# Schematic.net
KiCad netlist of a schematic drawn in Altium Designer
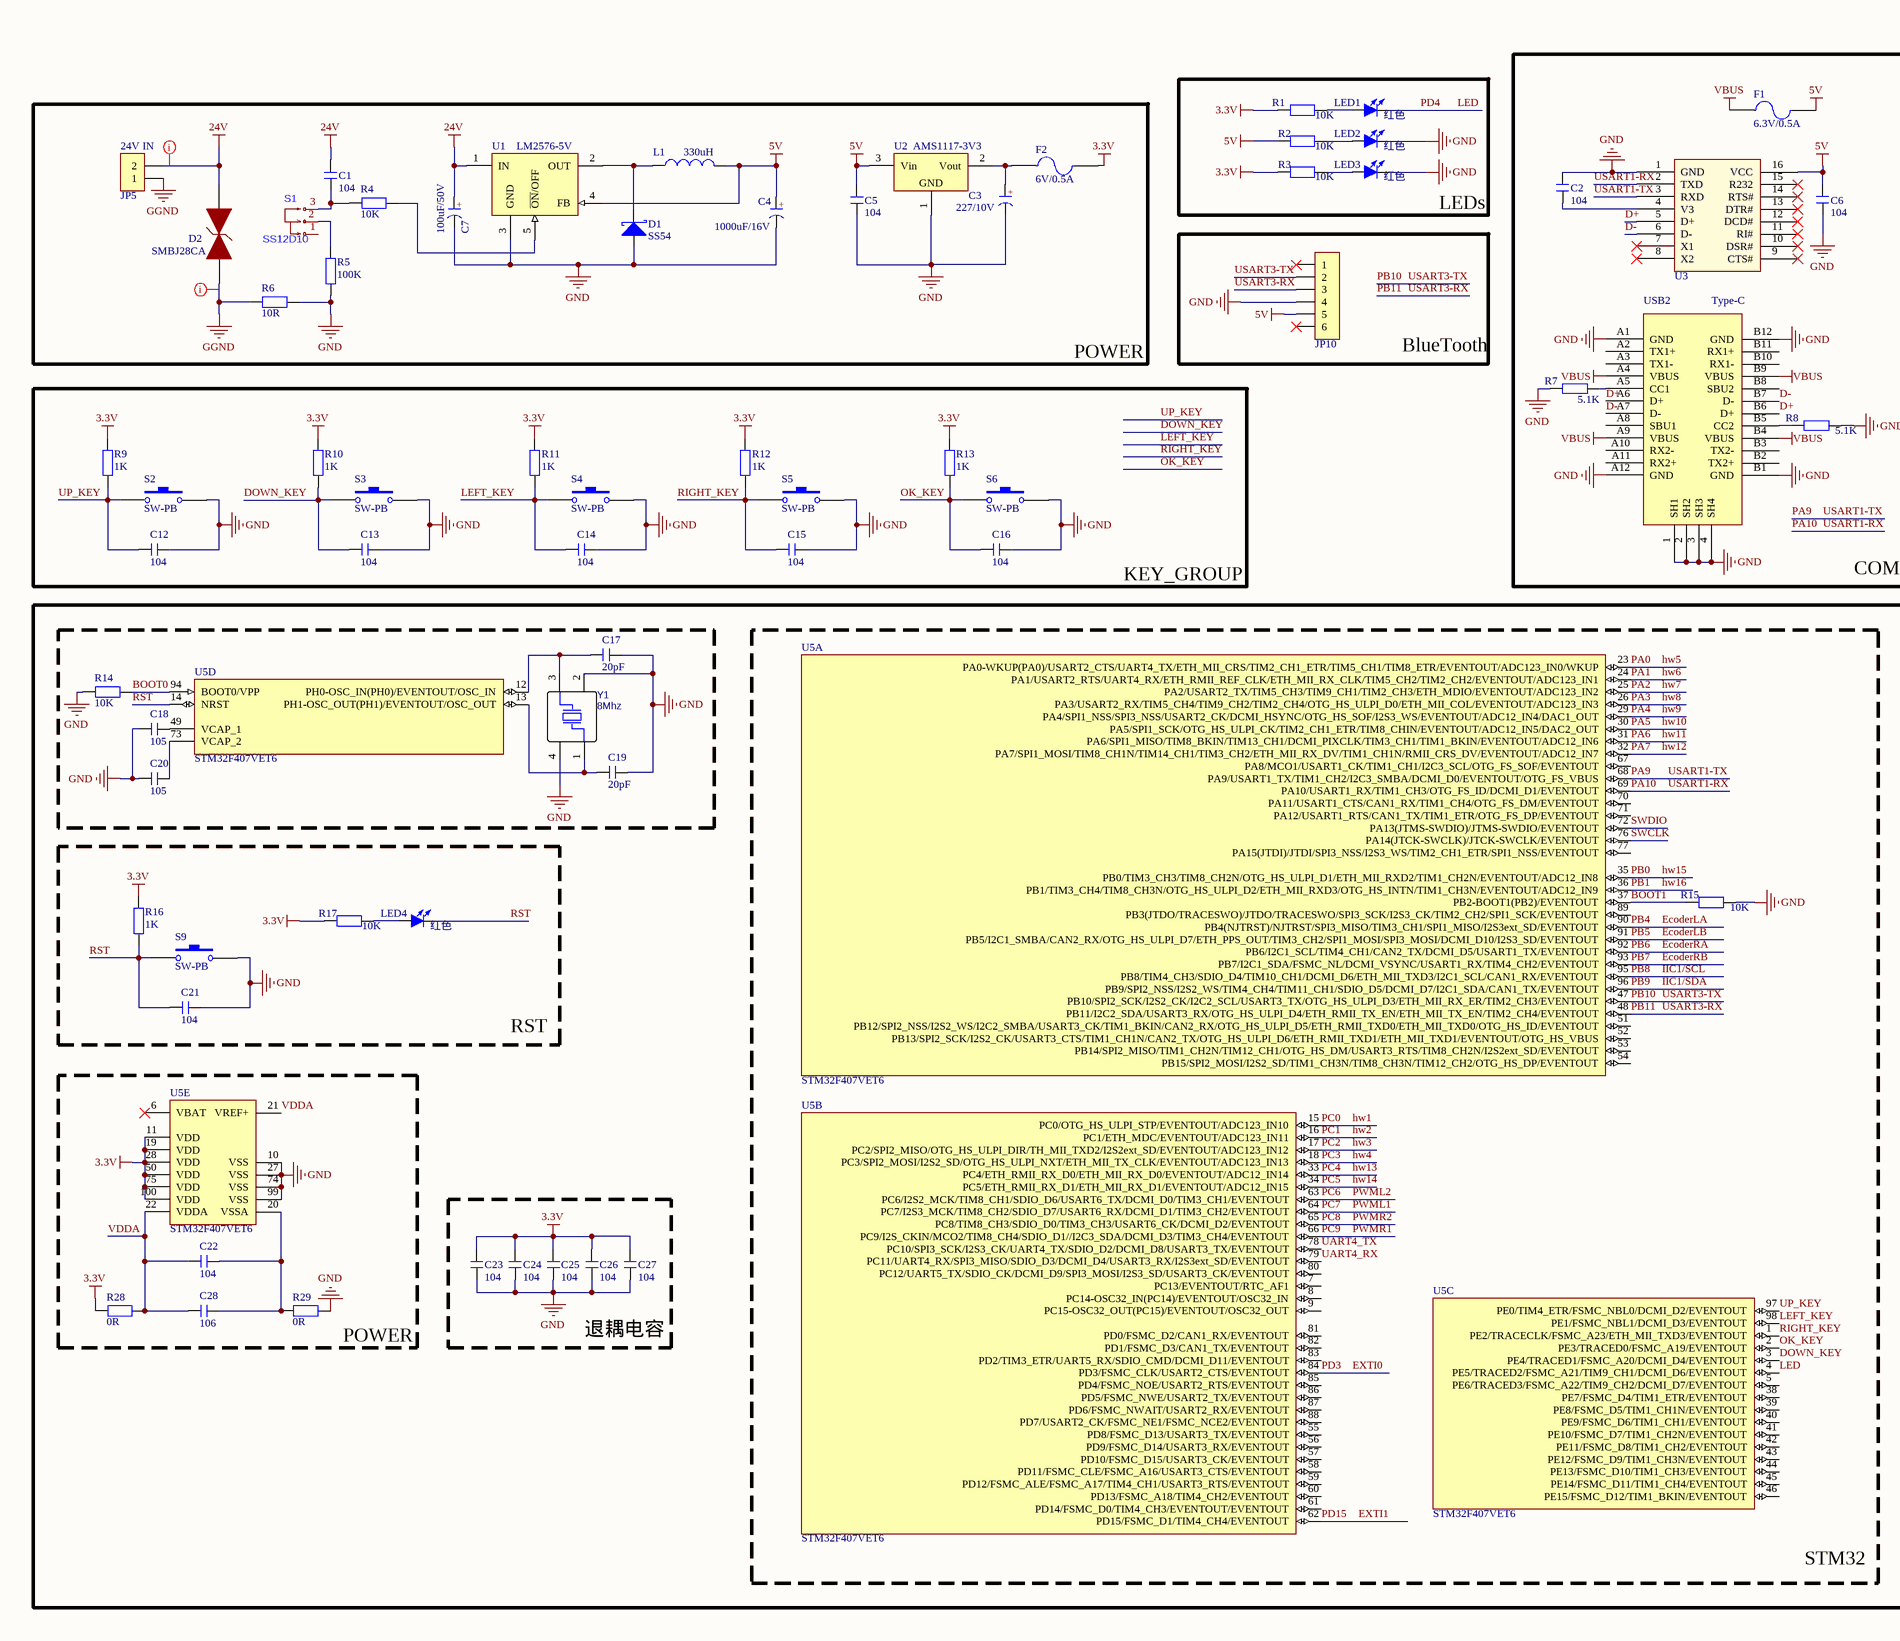
[diagram p0: Schematic.SchDoc, left]
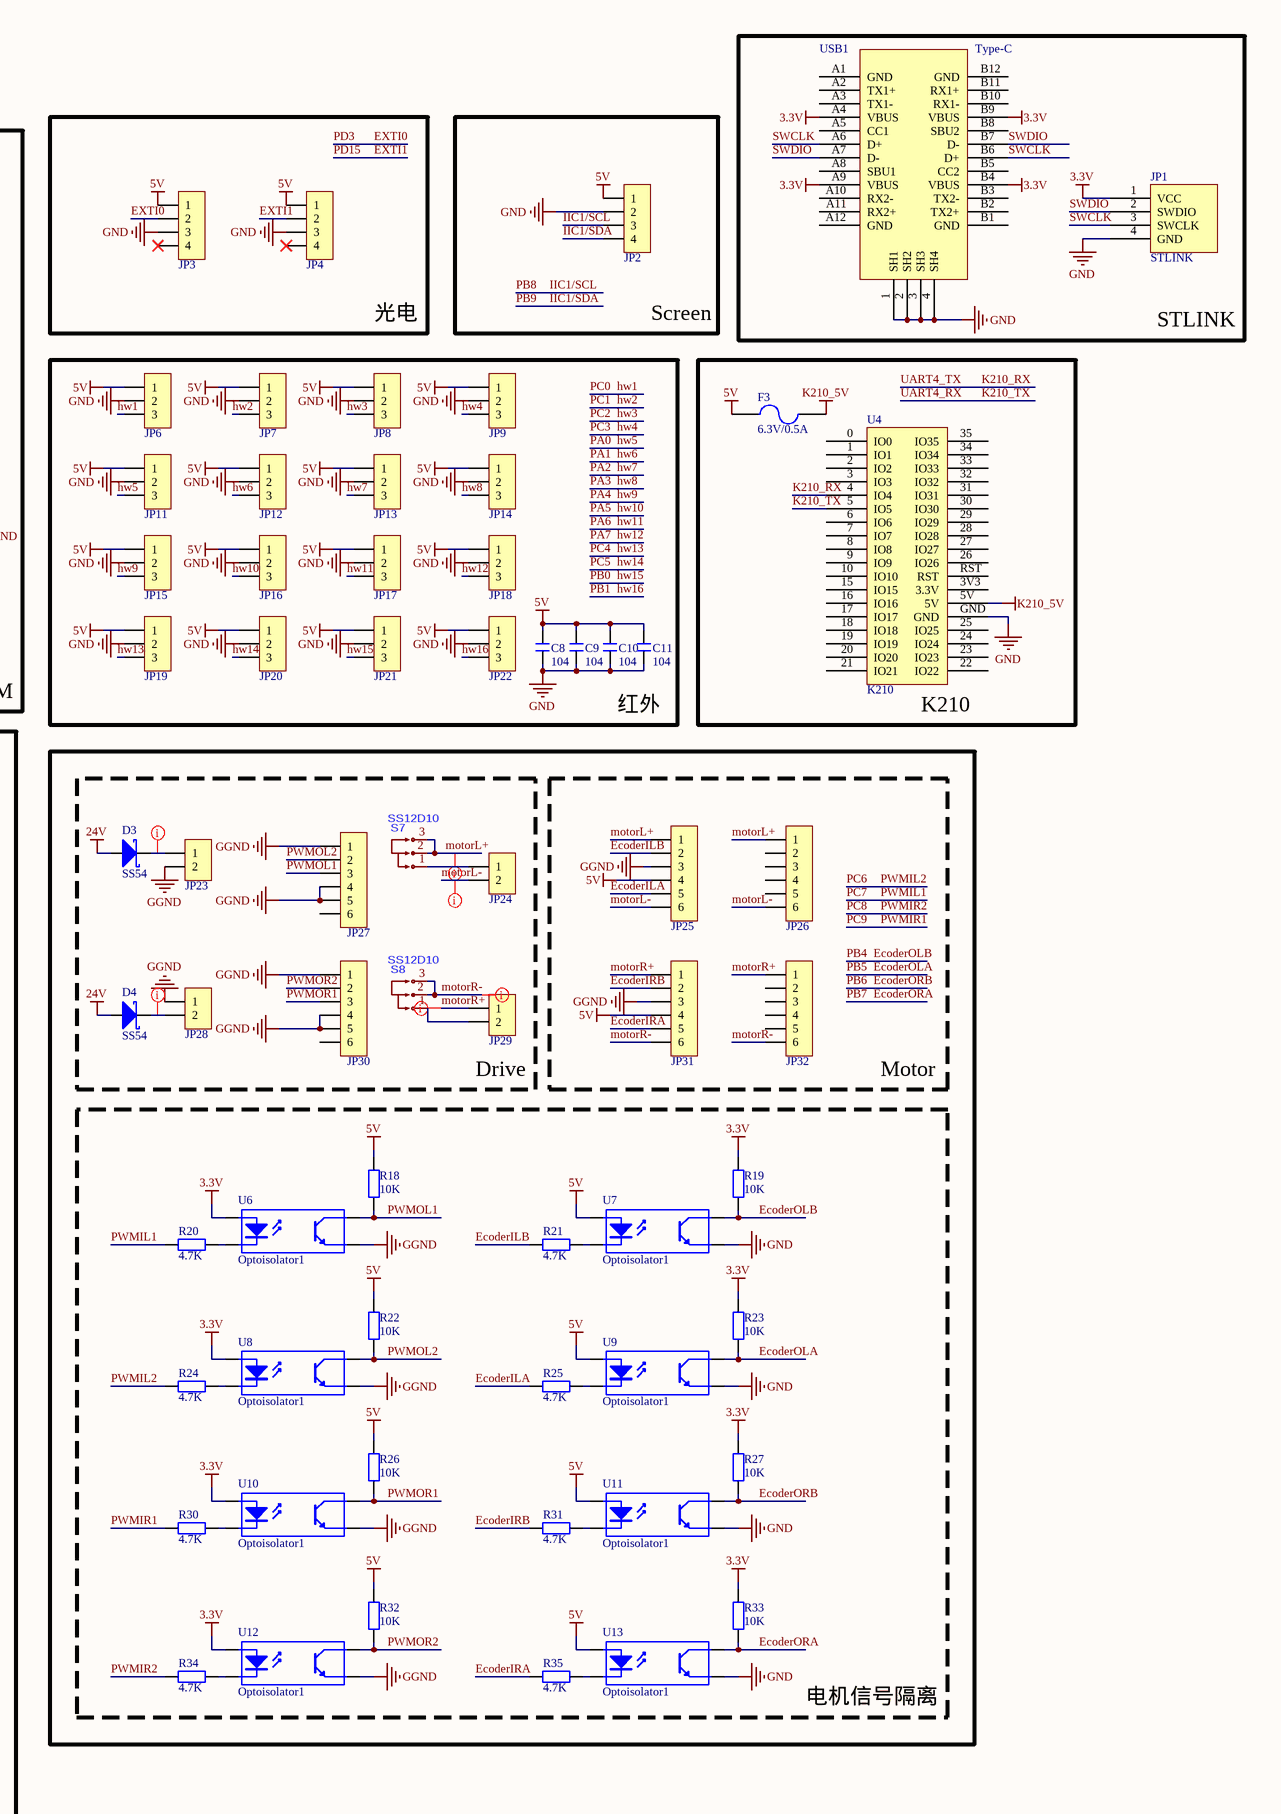
[diagram p1: Schematic.SchDoc, right]

(export (version "E")
  (design (tool "Eeschema 10.0.6"))
  (components
    (comp (ref "C1")
      (value "104")
      (footprint "C 0805_L")
      (description "贴片电容")
      (libsource (lib "0.1 - 电阻-电容-电感") (part "C"))
    )
    (comp (ref "C2") (value "104") (footprint "C 0805_L") (libsource (lib "0.1 - 电阻-电容-电感") (part "C")))
    (comp (ref "C3")
      (value "227/10V")
      (footprint "CM D(6.3*7.7)")
      (description "贴片钽电容")
      (libsource (lib "0.1 - 电阻-电容-电感") (part "CT"))
    )
    (comp (ref "C4")
      (value "1000uF/16V")
      (footprint "CAP 7.5*16*25 - GD")
      (description "直插电解电容")
      (libsource (lib "0.1 - 电阻-电容-电感") (part "CE"))
    )
    (comp (ref "C5")
      (value "104")
      (footprint "C 0805_L")
      (description "无极性贴片电容")
      (fields (field (name "版权归属") "源创客"))
      (libsource (lib "电阻-电容-电感") (part "C"))
    )
    (comp (ref "C6") (value "104") (footprint "C 0805_L") (libsource (lib "0.1 - 电阻-电容-电感") (part "C")))
    (comp (ref "C7")
      (value "100uF/50V")
      (footprint "CAP 3.5*8*11.5 - GD")
      (description "直插固态电容")
      (fields (field (name "版权归属") "封装库来自淘宝 ID：黄晶宝石"))
      (libsource (lib "0.1 - 电阻-电容-电感") (part "CS"))
    )
    (comp (ref "C8") (value "104") (footprint "C 0805_L") (libsource (lib "0.1 - 电阻-电容-电感") (part "C")))
    (comp (ref "C9") (value "104") (footprint "C 0805_L") (libsource (lib "0.1 - 电阻-电容-电感") (part "C")))
    (comp (ref "C10") (value "104") (footprint "C 0805_L") (libsource (lib "0.1 - 电阻-电容-电感") (part "C")))
    (comp (ref "C11") (value "104") (footprint "C 0805_L") (libsource (lib "0.1 - 电阻-电容-电感") (part "C")))
    (comp (ref "C12")
      (value "104")
      (footprint "C 0805_L")
      (description "贴片电容")
      (libsource (lib "0.1 - 电阻-电容-电感") (part "C"))
    )
    (comp (ref "C13")
      (value "104")
      (footprint "C 0805_L")
      (description "贴片电容")
      (libsource (lib "0.1 - 电阻-电容-电感") (part "C"))
    )
    (comp (ref "C14")
      (value "104")
      (footprint "C 0805_L")
      (description "贴片电容")
      (libsource (lib "0.1 - 电阻-电容-电感") (part "C"))
    )
    (comp (ref "C15")
      (value "104")
      (footprint "C 0805_L")
      (description "贴片电容")
      (libsource (lib "0.1 - 电阻-电容-电感") (part "C"))
    )
    (comp (ref "C16")
      (value "104")
      (footprint "C 0805_L")
      (description "贴片电容")
      (libsource (lib "0.1 - 电阻-电容-电感") (part "C"))
    )
    (comp (ref "C17")
      (value "20pF")
      (footprint "C 0805_L")
      (description "贴片电容")
      (libsource (lib "0.1 - 电阻-电容-电感") (part "C"))
    )
    (comp (ref "C18")
      (value "105")
      (footprint "C 0805_L")
      (description "贴片电容")
      (libsource (lib "0.1 - 电阻-电容-电感") (part "C"))
    )
    (comp (ref "C19")
      (value "20pF")
      (footprint "C 0805_L")
      (description "贴片电容")
      (libsource (lib "0.1 - 电阻-电容-电感") (part "C"))
    )
    (comp (ref "C20")
      (value "105")
      (footprint "C 0805_L")
      (description "贴片电容")
      (libsource (lib "0.1 - 电阻-电容-电感") (part "C"))
    )
    (comp (ref "C21")
      (value "104")
      (footprint "C 0805_L")
      (description "贴片电容")
      (libsource (lib "0.1 - 电阻-电容-电感") (part "C"))
    )
    (comp (ref "C22")
      (value "104")
      (footprint "C 0805_L")
      (description "贴片电容")
      (libsource (lib "0.1 - 电阻-电容-电感") (part "C"))
    )
    (comp (ref "C23")
      (value "104")
      (footprint "C 0805_L")
      (description "无极性贴片电容")
      (fields (field (name "版权归属") "源创客"))
      (libsource (lib "电阻-电容-电感") (part "C"))
    )
    (comp (ref "C24")
      (value "104")
      (footprint "C 0805_L")
      (description "无极性贴片电容")
      (fields (field (name "版权归属") "源创客"))
      (libsource (lib "电阻-电容-电感") (part "C"))
    )
    (comp (ref "C25")
      (value "104")
      (footprint "C 0805_L")
      (description "无极性贴片电容")
      (fields (field (name "版权归属") "源创客"))
      (libsource (lib "电阻-电容-电感") (part "C"))
    )
    (comp (ref "C26")
      (value "104")
      (footprint "C 0805_L")
      (description "无极性贴片电容")
      (fields (field (name "版权归属") "源创客"))
      (libsource (lib "电阻-电容-电感") (part "C"))
    )
    (comp (ref "C27")
      (value "104")
      (footprint "C 0805_L")
      (description "无极性贴片电容")
      (fields (field (name "版权归属") "源创客"))
      (libsource (lib "电阻-电容-电感") (part "C"))
    )
    (comp (ref "C28")
      (value "106")
      (footprint "C 0805_L")
      (description "贴片电容")
      (libsource (lib "0.1 - 电阻-电容-电感") (part "C"))
    )
    (comp (ref "D1")
      (value "SS54")
      (footprint "SMB/DO214AA")
      (description "肖特基二极管  30V/5A")
      (libsource (lib "0.2 -  二极管-整流桥") (part "1N5824"))
    )
    (comp (ref "D2")
      (value "SMBJ28CA")
      (footprint "SMB/DO214AA")
      (libsource (lib "MyPcbLib") (part "SMBJ28CA"))
    )
    (comp (ref "D3")
      (value "SS54")
      (footprint "SMB/DO214AA")
      (description "肖特基二极管  30V/5A")
      (libsource (lib "0.2 -  二极管-整流桥") (part "1N5824"))
    )
    (comp (ref "D4")
      (value "SS54")
      (footprint "SMB/DO214AA")
      (description "肖特基二极管  30V/5A")
      (libsource (lib "0.2 -  二极管-整流桥") (part "1N5824"))
    )
    (comp (ref "F1")
      (value "6.3V/0.5A")
      (footprint "C 0805_L")
      (description "Fuse")
      (fields (field (name "PUBLISHER") "Altium Limited"))
      (libsource (lib "Miscellaneous Devices") (part "Fuse 2"))
    )
    (comp (ref "F2")
      (value "6V/0.5A")
      (footprint "R 1206_L")
      (description "Fuse")
      (fields (field (name "PUBLISHER") "Altium Limited"))
      (libsource (lib "Miscellaneous Devices") (part "Fuse 2"))
    )
    (comp (ref "F3")
      (value "6.3V/0.5A")
      (footprint "C 0805_L")
      (description "Fuse")
      (fields (field (name "PUBLISHER") "Altium Limited"))
      (libsource (lib "Miscellaneous Devices") (part "Fuse 2"))
    )
    (comp (ref "JP1") (value "STLINK") (footprint "HDR2.54-LI-4P") (libsource (lib "SCHLib") (part "STLINK")))
    (comp (ref "JP2")
      (value "OLED")
      (footprint "OLED_0.96 4P")
      (libsource (lib "18 - 接插件-脚距2.54mm (100mil) ") (part "Header 4"))
    )
    (comp (ref "JP3")
      (value "光电")
      (footprint "XH2.54-LI-4P")
      (description "4P接插件")
      (libsource (lib "18 - 接插件-脚距2.54mm (100mil) ") (part "Header 4"))
    )
    (comp (ref "JP4")
      (value "光电")
      (footprint "XH2.54-LI-4P")
      (description "4P接插件")
      (libsource (lib "18 - 接插件-脚距2.54mm (100mil) ") (part "Header 4"))
    )
    (comp (ref "JP5")
      (value "24V IN")
      (footprint "KF128-5.08-2P")
      (description "2P接插件")
      (fields (field (name "版权归属") "封装库来自淘宝卖家 ID：黄晶宝石"))
      (libsource (lib "") (part "Header 2_1"))
    )
    (comp (ref "JP6")
      (value "红外")
      (footprint "PH2.0-LI-3P")
      (description "3P接插件")
      (fields (field (name "版权归属") "源创客"))
      (libsource (lib "p-接插件") (part "Header 3"))
    )
    (comp (ref "JP7")
      (value "红外")
      (footprint "PH2.0-LI-3P")
      (description "3P接插件")
      (fields (field (name "版权归属") "源创客"))
      (libsource (lib "p-接插件") (part "Header 3"))
    )
    (comp (ref "JP8")
      (value "红外")
      (footprint "PH2.0-LI-3P")
      (description "3P接插件")
      (fields (field (name "版权归属") "源创客"))
      (libsource (lib "p-接插件") (part "Header 3"))
    )
    (comp (ref "JP9")
      (value "红外")
      (footprint "PH2.0-LI-3P")
      (description "3P接插件")
      (fields (field (name "版权归属") "源创客"))
      (libsource (lib "p-接插件") (part "Header 3"))
    )
    (comp (ref "JP10")
      (value "蓝牙")
      (footprint "HDR2.54-LI-6P")
      (description "6P接插件")
      (libsource (lib "18 - 接插件-脚距2.54mm (100mil) ") (part "Header 6"))
    )
    (comp (ref "JP11")
      (value "红外")
      (footprint "PH2.0-LI-3P")
      (description "3P接插件")
      (fields (field (name "版权归属") "源创客"))
      (libsource (lib "p-接插件") (part "Header 3"))
    )
    (comp (ref "JP12")
      (value "红外")
      (footprint "PH2.0-LI-3P")
      (description "3P接插件")
      (fields (field (name "版权归属") "源创客"))
      (libsource (lib "p-接插件") (part "Header 3"))
    )
    (comp (ref "JP13")
      (value "红外")
      (footprint "PH2.0-LI-3P")
      (description "3P接插件")
      (fields (field (name "版权归属") "源创客"))
      (libsource (lib "p-接插件") (part "Header 3"))
    )
    (comp (ref "JP14")
      (value "红外")
      (footprint "PH2.0-LI-3P")
      (description "3P接插件")
      (fields (field (name "版权归属") "源创客"))
      (libsource (lib "p-接插件") (part "Header 3"))
    )
    (comp (ref "JP15")
      (value "红外")
      (footprint "PH2.0-LI-3P")
      (description "3P接插件")
      (fields (field (name "版权归属") "源创客"))
      (libsource (lib "p-接插件") (part "Header 3"))
    )
    (comp (ref "JP16")
      (value "红外")
      (footprint "PH2.0-LI-3P")
      (description "3P接插件")
      (fields (field (name "版权归属") "源创客"))
      (libsource (lib "p-接插件") (part "Header 3"))
    )
    (comp (ref "JP17")
      (value "红外")
      (footprint "PH2.0-LI-3P")
      (description "3P接插件")
      (fields (field (name "版权归属") "源创客"))
      (libsource (lib "p-接插件") (part "Header 3"))
    )
    (comp (ref "JP18")
      (value "红外")
      (footprint "PH2.0-LI-3P")
      (description "3P接插件")
      (fields (field (name "版权归属") "源创客"))
      (libsource (lib "p-接插件") (part "Header 3"))
    )
    (comp (ref "JP19")
      (value "红外")
      (footprint "PH2.0-LI-3P")
      (description "3P接插件")
      (fields (field (name "版权归属") "源创客"))
      (libsource (lib "p-接插件") (part "Header 3"))
    )
    (comp (ref "JP20")
      (value "红外")
      (footprint "PH2.0-LI-3P")
      (description "3P接插件")
      (fields (field (name "版权归属") "源创客"))
      (libsource (lib "p-接插件") (part "Header 3"))
    )
    (comp (ref "JP21")
      (value "红外")
      (footprint "PH2.0-LI-3P")
      (description "3P接插件")
      (fields (field (name "版权归属") "源创客"))
      (libsource (lib "p-接插件") (part "Header 3"))
    )
    (comp (ref "JP22")
      (value "红外")
      (footprint "PH2.0-LI-3P")
      (description "3P接插件")
      (fields (field (name "版权归属") "源创客"))
      (libsource (lib "p-接插件") (part "Header 3"))
    )
    (comp (ref "JP23")
      (value "驱动1")
      (footprint "KF128-5.08-2P")
      (description "2P接插件")
      (fields (field (name "版权归属") "封装库来自淘宝卖家 ID：黄晶宝石"))
      (libsource (lib "6.1 - 接插件-脚距5.08 (200mil) ") (part "Header 2"))
    )
    (comp (ref "JP24")
      (value "驱动输出1")
      (footprint "KF128-5.08-2P")
      (description "2P接插件")
      (fields (field (name "版权归属") "封装库来自淘宝卖家 ID：黄晶宝石"))
      (libsource (lib "6.1 - 接插件-脚距5.08 (200mil) ") (part "Header 2"))
    )
    (comp (ref "JP25")
      (value "电机1")
      (footprint "XH2.54-LI-6P")
      (description "6P接插件")
      (fields (field (name "版权归属") "封装库来自淘宝 ID：黄晶宝石"))
      (libsource (lib "5.4 - 接插件-脚距2.54 (100mil) ") (part "Header 6"))
    )
    (comp (ref "JP26")
      (value "电机1p")
      (footprint "XH2.54-LI-6P")
      (description "6P接插件")
      (libsource (lib "18 - 接插件-脚距2.54mm (100mil) ") (part "Header 6"))
    )
    (comp (ref "JP27")
      (value "驱动pwm1")
      (footprint "XH2.54-LI-6P")
      (description "6P接插件")
      (fields (field (name "版权归属") "封装库来自淘宝 ID：黄晶宝石"))
      (libsource (lib "5.4 - 接插件-脚距2.54 (100mil) ") (part "Header 6"))
    )
    (comp (ref "JP28")
      (value "驱动2")
      (footprint "KF128-5.08-2P")
      (description "2P接插件")
      (fields (field (name "版权归属") "封装库来自淘宝卖家 ID：黄晶宝石"))
      (libsource (lib "6.1 - 接插件-脚距5.08 (200mil) ") (part "Header 2"))
    )
    (comp (ref "JP29")
      (value "驱动输出1")
      (footprint "KF128-5.08-2P")
      (description "2P接插件")
      (fields (field (name "版权归属") "封装库来自淘宝卖家 ID：黄晶宝石"))
      (libsource (lib "6.1 - 接插件-脚距5.08 (200mil) ") (part "Header 2"))
    )
    (comp (ref "JP30")
      (value "驱动pwm2")
      (footprint "XH2.54-LI-6P")
      (description "6P接插件")
      (fields (field (name "版权归属") "封装库来自淘宝 ID：黄晶宝石"))
      (libsource (lib "5.4 - 接插件-脚距2.54 (100mil) ") (part "Header 6"))
    )
    (comp (ref "JP31")
      (value "电机2")
      (footprint "XH2.54-LI-6P")
      (description "6P接插件")
      (fields (field (name "版权归属") "封装库来自淘宝 ID：黄晶宝石"))
      (libsource (lib "5.4 - 接插件-脚距2.54 (100mil) ") (part "Header 6"))
    )
    (comp (ref "JP32")
      (value "电机2p")
      (footprint "XH2.54-LI-6P")
      (description "6P接插件")
      (libsource (lib "18 - 接插件-脚距2.54mm (100mil) ") (part "Header 6"))
    )
    (comp (ref "L1")
      (value "330uH")
      (footprint "CDRH125")
      (description "Inductor")
      (fields (field (name "PUBLISHER") "Altium Limited"))
      (libsource (lib "安中医库2.0") (part "电感直插"))
    )
    (comp (ref "LED1")
      (value "红色")
      (footprint "LED 0805G")
      (description "贴片LED")
      (fields (field (name "版权归属") "封装库来自淘宝 ID：黄晶宝石"))
      (libsource (lib "0.3 - LED发光二极管") (part "LED-SMD"))
    )
    (comp (ref "LED2")
      (value "红色")
      (footprint "LED 0805G")
      (description "贴片LED")
      (fields (field (name "版权归属") "封装库来自淘宝 ID：黄晶宝石"))
      (libsource (lib "0.3 - LED发光二极管") (part "LED-SMD"))
    )
    (comp (ref "LED3")
      (value "红色")
      (footprint "LED 0805G")
      (description "贴片LED")
      (fields (field (name "版权归属") "封装库来自淘宝 ID：黄晶宝石"))
      (libsource (lib "0.3 - LED发光二极管") (part "LED-SMD"))
    )
    (comp (ref "LED4")
      (value "红色")
      (footprint "LED 0805G")
      (description "贴片LED")
      (fields (field (name "版权归属") "封装库来自淘宝 ID：黄晶宝石"))
      (libsource (lib "0.3 - LED发光二极管") (part "LED-SMD"))
    )
    (comp (ref "R1")
      (value "10K")
      (footprint "R 0805_L")
      (description "贴片电阻")
      (fields (field (name "版权归属") "来自淘宝 ID：黄晶宝石"))
      (libsource (lib "0.1 - 电阻-电容-电感") (part "R"))
    )
    (comp (ref "R2")
      (value "10K")
      (footprint "R 0805_L")
      (description "贴片电阻")
      (fields (field (name "版权归属") "来自淘宝 ID：黄晶宝石"))
      (libsource (lib "0.1 - 电阻-电容-电感") (part "R"))
    )
    (comp (ref "R3")
      (value "10K")
      (footprint "R 0805_L")
      (description "贴片电阻")
      (fields (field (name "版权归属") "来自淘宝 ID：黄晶宝石"))
      (libsource (lib "0.1 - 电阻-电容-电感") (part "R"))
    )
    (comp (ref "R4")
      (value "10K")
      (footprint "R 0805_L")
      (description "贴片电阻")
      (fields (field (name "版权归属") "来自淘宝 ID：黄晶宝石"))
      (libsource (lib "0.1 - 电阻-电容-电感") (part "R"))
    )
    (comp (ref "R5")
      (value "100K")
      (footprint "R 0805_L")
      (description "贴片电阻")
      (fields (field (name "版权归属") "来自淘宝 ID：黄晶宝石"))
      (libsource (lib "0.1 - 电阻-电容-电感") (part "R"))
    )
    (comp (ref "R6")
      (value "10R")
      (footprint "R 0805_L")
      (description "贴片电阻")
      (fields (field (name "版权归属") "来自淘宝 ID：黄晶宝石"))
      (libsource (lib "0.1 - 电阻-电容-电感") (part "R"))
    )
    (comp (ref "R7") (value "5.1K") (footprint "R 0805_L") (libsource (lib "EXPLORER") (part "R")))
    (comp (ref "R8") (value "5.1K") (footprint "R 0805_L") (libsource (lib "EXPLORER") (part "R")))
    (comp (ref "R9")
      (value "1K")
      (footprint "R 0805_L")
      (description "贴片电阻")
      (fields (field (name "版权归属") "来自淘宝 ID：黄晶宝石"))
      (libsource (lib "0.1 - 电阻-电容-电感") (part "R"))
    )
    (comp (ref "R10")
      (value "1K")
      (footprint "R 0805_L")
      (description "贴片电阻")
      (fields (field (name "版权归属") "来自淘宝 ID：黄晶宝石"))
      (libsource (lib "0.1 - 电阻-电容-电感") (part "R"))
    )
    (comp (ref "R11")
      (value "1K")
      (footprint "R 0805_L")
      (description "贴片电阻")
      (fields (field (name "版权归属") "来自淘宝 ID：黄晶宝石"))
      (libsource (lib "0.1 - 电阻-电容-电感") (part "R"))
    )
    (comp (ref "R12")
      (value "1K")
      (footprint "R 0805_L")
      (description "贴片电阻")
      (fields (field (name "版权归属") "来自淘宝 ID：黄晶宝石"))
      (libsource (lib "0.1 - 电阻-电容-电感") (part "R"))
    )
    (comp (ref "R13")
      (value "1K")
      (footprint "R 0805_L")
      (description "贴片电阻")
      (fields (field (name "版权归属") "来自淘宝 ID：黄晶宝石"))
      (libsource (lib "0.1 - 电阻-电容-电感") (part "R"))
    )
    (comp (ref "R14")
      (value "10K")
      (footprint "R 0805_L")
      (description "贴片电阻")
      (fields (field (name "版权归属") "来自淘宝 ID：黄晶宝石"))
      (libsource (lib "0.1 - 电阻-电容-电感") (part "R"))
    )
    (comp (ref "R15")
      (value "10K")
      (footprint "R 0805_L")
      (description "贴片电阻")
      (fields (field (name "版权归属") "来自淘宝 ID：黄晶宝石"))
      (libsource (lib "0.1 - 电阻-电容-电感") (part "R"))
    )
    (comp (ref "R16")
      (value "1K")
      (footprint "R 0805_L")
      (description "贴片电阻")
      (fields (field (name "版权归属") "来自淘宝 ID：黄晶宝石"))
      (libsource (lib "0.1 - 电阻-电容-电感") (part "R"))
    )
    (comp (ref "R17")
      (value "10K")
      (footprint "R 0805_L")
      (description "贴片电阻")
      (fields (field (name "版权归属") "来自淘宝 ID：黄晶宝石"))
      (libsource (lib "0.1 - 电阻-电容-电感") (part "R"))
    )
    (comp (ref "R18")
      (value "10K")
      (footprint "R 0805_L")
      (description "Resistor")
      (fields (field (name "PUBLISHER") "Altium Limited"))
      (libsource (lib "") (part "Res2_1"))
    )
    (comp (ref "R19")
      (value "10K")
      (footprint "R 0805_L")
      (description "Resistor")
      (fields (field (name "PUBLISHER") "Altium Limited"))
      (libsource (lib "") (part "Res2_1"))
    )
    (comp (ref "R20")
      (value "4.7K")
      (footprint "R 0805_L")
      (description "Resistor")
      (fields (field (name "PUBLISHER") "Altium Limited"))
      (libsource (lib "Miscellaneous Devices") (part "Res2"))
    )
    (comp (ref "R21")
      (value "4.7K")
      (footprint "R 0805_L")
      (description "Resistor")
      (fields (field (name "PUBLISHER") "Altium Limited"))
      (libsource (lib "Miscellaneous Devices") (part "Res2"))
    )
    (comp (ref "R22")
      (value "10K")
      (footprint "R 0805_L")
      (description "Resistor")
      (fields (field (name "PUBLISHER") "Altium Limited"))
      (libsource (lib "") (part "Res2_1"))
    )
    (comp (ref "R23")
      (value "10K")
      (footprint "R 0805_L")
      (description "Resistor")
      (fields (field (name "PUBLISHER") "Altium Limited"))
      (libsource (lib "") (part "Res2_1"))
    )
    (comp (ref "R24")
      (value "4.7K")
      (footprint "R 0805_L")
      (description "Resistor")
      (fields (field (name "PUBLISHER") "Altium Limited"))
      (libsource (lib "Miscellaneous Devices") (part "Res2"))
    )
    (comp (ref "R25")
      (value "4.7K")
      (footprint "R 0805_L")
      (description "Resistor")
      (fields (field (name "PUBLISHER") "Altium Limited"))
      (libsource (lib "Miscellaneous Devices") (part "Res2"))
    )
    (comp (ref "R26")
      (value "10K")
      (footprint "R 0805_L")
      (description "Resistor")
      (fields (field (name "PUBLISHER") "Altium Limited"))
      (libsource (lib "") (part "Res2_1"))
    )
    (comp (ref "R27")
      (value "10K")
      (footprint "R 0805_L")
      (description "Resistor")
      (fields (field (name "PUBLISHER") "Altium Limited"))
      (libsource (lib "") (part "Res2_1"))
    )
    (comp (ref "R28")
      (value "0R")
      (footprint "R 0805_L")
      (description "贴片电阻")
      (fields (field (name "版权归属") "来自淘宝 ID：黄晶宝石"))
      (libsource (lib "0.1 - 电阻-电容-电感") (part "R"))
    )
    (comp (ref "R29")
      (value "0R")
      (footprint "R 0805_L")
      (description "贴片电阻")
      (fields (field (name "版权归属") "来自淘宝 ID：黄晶宝石"))
      (libsource (lib "0.1 - 电阻-电容-电感") (part "R"))
    )
    (comp (ref "R30")
      (value "4.7K")
      (footprint "R 0805_L")
      (description "Resistor")
      (fields (field (name "PUBLISHER") "Altium Limited"))
      (libsource (lib "Miscellaneous Devices") (part "Res2"))
    )
    (comp (ref "R31")
      (value "4.7K")
      (footprint "R 0805_L")
      (description "Resistor")
      (fields (field (name "PUBLISHER") "Altium Limited"))
      (libsource (lib "Miscellaneous Devices") (part "Res2"))
    )
    (comp (ref "R32")
      (value "10K")
      (footprint "R 0805_L")
      (description "Resistor")
      (fields (field (name "PUBLISHER") "Altium Limited"))
      (libsource (lib "") (part "Res2_1"))
    )
    (comp (ref "R33")
      (value "10K")
      (footprint "R 0805_L")
      (description "Resistor")
      (fields (field (name "PUBLISHER") "Altium Limited"))
      (libsource (lib "") (part "Res2_1"))
    )
    (comp (ref "R34")
      (value "4.7K")
      (footprint "R 0805_L")
      (description "Resistor")
      (fields (field (name "PUBLISHER") "Altium Limited"))
      (libsource (lib "Miscellaneous Devices") (part "Res2"))
    )
    (comp (ref "R35")
      (value "4.7K")
      (footprint "R 0805_L")
      (description "Resistor")
      (fields (field (name "PUBLISHER") "Altium Limited"))
      (libsource (lib "Miscellaneous Devices") (part "Res2"))
    )
    (comp (ref "S1")
      (value "SS12D10")
      (footprint "SS-12D10")
      (libsource (lib "combat") (part "SS12D10G4 071"))
    )
    (comp (ref "S2")
      (value "SW-PB")
      (footprint "TSW SMD-6*6*4.3")
      (description "微动开关")
      (fields (field (name "PUBLISHER") "Altium Limited"))
      (libsource (lib "0.7 - 常用按键-开关") (part "SW-PB"))
    )
    (comp (ref "S3")
      (value "SW-PB")
      (footprint "TSW SMD-6*6*4.3")
      (description "微动开关")
      (fields (field (name "PUBLISHER") "Altium Limited"))
      (libsource (lib "0.7 - 常用按键-开关") (part "SW-PB"))
    )
    (comp (ref "S4")
      (value "SW-PB")
      (footprint "TSW SMD-6*6*4.3")
      (description "微动开关")
      (fields (field (name "PUBLISHER") "Altium Limited"))
      (libsource (lib "0.7 - 常用按键-开关") (part "SW-PB"))
    )
    (comp (ref "S5")
      (value "SW-PB")
      (footprint "TSW SMD-6*6*4.3")
      (description "微动开关")
      (fields (field (name "PUBLISHER") "Altium Limited"))
      (libsource (lib "0.7 - 常用按键-开关") (part "SW-PB"))
    )
    (comp (ref "S6")
      (value "SW-PB")
      (footprint "TSW SMD-6*6*4.3")
      (description "微动开关")
      (fields (field (name "PUBLISHER") "Altium Limited"))
      (libsource (lib "0.7 - 常用按键-开关") (part "SW-PB"))
    )
    (comp (ref "S7")
      (value "SS12D10")
      (footprint "SS-12D10")
      (libsource (lib "combat") (part "SS12D10G4 071"))
    )
    (comp (ref "S8")
      (value "SS12D10")
      (footprint "SS-12D10")
      (libsource (lib "combat") (part "SS12D10G4 071"))
    )
    (comp (ref "S9")
      (value "SW-PB")
      (footprint "TSW SMD-3*6*2.5")
      (description "微动开关")
      (fields (field (name "PUBLISHER") "Altium Limited"))
      (libsource (lib "0.7 - 常用按键-开关") (part "SW-PB"))
    )
    (comp (ref "U1")
      (value "LM2576-5V")
      (footprint "TO263-5A")
      (description "DC降压芯片")
      (libsource (lib "1.1 - 电源类芯片") (part "LM2596-ADJ"))
    )
    (comp (ref "U2")
      (value "AMS1117-3V3")
      (footprint "SOT223_L")
      (description "三端稳压芯片")
      (libsource (lib "1.1 - 电源类芯片") (part "AMS1117"))
    )
    (comp (ref "U3")
      (value "CH340C")
      (footprint "sop16_L")
      (libsource (lib "1.9 - CH340系列编程器芯片") (part "CH340G"))
    )
    (comp (ref "U4") (value "K210") (footprint "K210") (libsource (lib "SCHLib") (part "K210")))
    (comp (ref "U5")
      (value "STM32F407VET6")
      (footprint "LQFP100 14x14_M")
      (libsource (lib "SCHLib") (part "STM32F407VET6"))
    )
    (comp (ref "U6")
      (value "Optoisolator1")
      (footprint "SOP4-W2.54_M")
      (description "光耦隔离")
      (fields (field (name "PUBLISHER") "Altium Limited"))
      (libsource (lib "Miscellaneous Devices") (part "Optoisolator1"))
    )
    (comp (ref "U7")
      (value "Optoisolator1")
      (footprint "SOP4-W2.54_M")
      (description "光耦隔离")
      (fields (field (name "PUBLISHER") "Altium Limited"))
      (libsource (lib "Miscellaneous Devices") (part "Optoisolator1"))
    )
    (comp (ref "U8")
      (value "Optoisolator1")
      (footprint "SOP4-W2.54_M")
      (description "光耦隔离")
      (fields (field (name "PUBLISHER") "Altium Limited"))
      (libsource (lib "Miscellaneous Devices") (part "Optoisolator1"))
    )
    (comp (ref "U9")
      (value "Optoisolator1")
      (footprint "SOP4-W2.54_M")
      (description "光耦隔离")
      (fields (field (name "PUBLISHER") "Altium Limited"))
      (libsource (lib "Miscellaneous Devices") (part "Optoisolator1"))
    )
    (comp (ref "U10")
      (value "Optoisolator1")
      (footprint "SOP4-W2.54_M")
      (description "光耦隔离")
      (fields (field (name "PUBLISHER") "Altium Limited"))
      (libsource (lib "Miscellaneous Devices") (part "Optoisolator1"))
    )
    (comp (ref "U11")
      (value "Optoisolator1")
      (footprint "SOP4-W2.54_M")
      (description "光耦隔离")
      (fields (field (name "PUBLISHER") "Altium Limited"))
      (libsource (lib "Miscellaneous Devices") (part "Optoisolator1"))
    )
    (comp (ref "U12")
      (value "Optoisolator1")
      (footprint "SOP4-W2.54_M")
      (description "光耦隔离")
      (fields (field (name "PUBLISHER") "Altium Limited"))
      (libsource (lib "Miscellaneous Devices") (part "Optoisolator1"))
    )
    (comp (ref "U13")
      (value "Optoisolator1")
      (footprint "SOP4-W2.54_M")
      (description "光耦隔离")
      (fields (field (name "PUBLISHER") "Altium Limited"))
      (libsource (lib "Miscellaneous Devices") (part "Optoisolator1"))
    )
    (comp (ref "USB1")
      (value "Type-C")
      (footprint "USBTypeC-16P")
      (libsource (lib "MyPcbLib") (part "USB-Type-C-TOP"))
    )
    (comp (ref "USB2")
      (value "Type-C")
      (footprint "USBTypeC-16P")
      (libsource (lib "MyPcbLib") (part "USB-Type-C-TOP"))
    )
    (comp (ref "Y1")
      (value "8Mhz")
      (footprint "OSC 5032-4P")
      (fields
        (field (name "BOM_MANUFACTURER PART") "X322516MLB4SI")
        (field (name "BOM_SUPPLIER PART") "C13738")
      )
      (libsource (lib "EXPLORER") (part "Y"))
    )
  )
  (nets
    (net (code "1") (name "/BOOT0") (class "Default")
      (node (ref "R14") (pin "2") (pinfunction "2_2") (pintype "passive"))
      (node (ref "U5") (pin "94") (pinfunction "BOOT0/VPP_94") (pintype "input"))
    )
    (net (code "2") (name "/BOOT1") (class "Default")
      (node (ref "R15") (pin "2") (pinfunction "2_2") (pintype "passive"))
      (node (ref "U5") (pin "37") (pinfunction "PB2-BOOT1(PB2)/EVENTOUT_37") (pintype "bidirectional"))
    )
    (net (code "3") (name "/D+") (class "Default")
      (node (ref "U3") (pin "5") (pinfunction "D+_5") (pintype "passive"))
      (node (ref "USB2") (pin "A6") (pinfunction "D+_A6") (pintype "passive"))
      (node (ref "USB2") (pin "B6") (pinfunction "D+_B6") (pintype "passive"))
    )
    (net (code "4") (name "/D-") (class "Default")
      (node (ref "U3") (pin "6") (pinfunction "D-_6") (pintype "passive"))
      (node (ref "USB2") (pin "A7") (pinfunction "D-_A7") (pintype "passive"))
      (node (ref "USB2") (pin "B7") (pinfunction "D-_B7") (pintype "passive"))
    )
    (net (code "5") (name "/DOWN_KEY") (class "Default")
      (node (ref "C13") (pin "1") (pinfunction "1_1") (pintype "passive"))
      (node (ref "R10") (pin "2") (pinfunction "2_2") (pintype "passive"))
      (node (ref "S3") (pin "1") (pinfunction "1_1") (pintype "passive"))
      (node (ref "U5") (pin "3") (pinfunction "PE4/TRACED1/FSMC_A20/DCMI_D4/EVENTOUT_3") (pintype "bidirectional"))
    )
    (net (code "6") (name "/EXTI0") (class "Default")
      (node (ref "JP3") (pin "2") (pinfunction "2_2") (pintype "passive"))
      (node (ref "U5") (pin "84") (pinfunction "PD3/FSMC_CLK/USART2_CTS/EVENTOUT_84") (pintype "bidirectional"))
    )
    (net (code "7") (name "/EXTI1") (class "Default")
      (node (ref "JP4") (pin "2") (pinfunction "2_2") (pintype "passive"))
      (node (ref "U5") (pin "62") (pinfunction "PD15/FSMC_D1/TIM4_CH4/EVENTOUT_62") (pintype "bidirectional"))
    )
    (net (code "8") (name "/EcoderILA") (class "Default")
      (node (ref "JP25") (pin "5") (pinfunction "5_5") (pintype "passive"))
      (node (ref "R25") (pin "1") (pinfunction "1_1") (pintype "passive"))
    )
    (net (code "9") (name "/EcoderILB") (class "Default")
      (node (ref "JP25") (pin "2") (pinfunction "2_2") (pintype "passive"))
      (node (ref "R21") (pin "1") (pinfunction "1_1") (pintype "passive"))
    )
    (net (code "10") (name "/EcoderIRA") (class "Default")
      (node (ref "JP31") (pin "5") (pinfunction "5_5") (pintype "passive"))
      (node (ref "R35") (pin "1") (pinfunction "1_1") (pintype "passive"))
    )
    (net (code "11") (name "/EcoderIRB") (class "Default")
      (node (ref "JP31") (pin "2") (pinfunction "2_2") (pintype "passive"))
      (node (ref "R31") (pin "1") (pinfunction "1_1") (pintype "passive"))
    )
    (net (code "12") (name "/EcoderLA") (class "Default")
      (node (ref "R19") (pin "2") (pinfunction "2_2") (pintype "passive"))
      (node (ref "U5") (pin "90") (pinfunction "PB4(NJTRST)/NJTRST/SPI3_MISO/TIM3_CH1/SPI1_MISO/I2S3ext_SD/EVENTOUT_90") (pintype "bidirectional"))
      (node (ref "U7") (pin "4") (pinfunction "C_4") (pintype "passive"))
    )
    (net (code "13") (name "/EcoderLB") (class "Default")
      (node (ref "R23") (pin "2") (pinfunction "2_2") (pintype "passive"))
      (node (ref "U5") (pin "91") (pinfunction "PB5/I2C1_SMBA/CAN2_RX/OTG_HS_ULPI_D7/ETH_PPS_OUT/TIM3_CH2/SPI1_MOSI/SPI3_MOSI/DCMI_D10/I2S3_SD/EVENTOUT_91") (pintype "bidirectional"))
      (node (ref "U9") (pin "4") (pinfunction "C_4") (pintype "passive"))
    )
    (net (code "14") (name "/EcoderORA") (class "Default")
      (node (ref "R33") (pin "2") (pinfunction "2_2") (pintype "passive"))
      (node (ref "U13") (pin "4") (pinfunction "C_4") (pintype "passive"))
      (node (ref "U5") (pin "93") (pinfunction "PB7/I2C1_SDA/FSMC_NL/DCMI_VSYNC/USART1_RX/TIM4_CH2/EVENTOUT_93") (pintype "bidirectional"))
    )
    (net (code "15") (name "/EcoderORB") (class "Default")
      (node (ref "R27") (pin "2") (pinfunction "2_2") (pintype "passive"))
      (node (ref "U11") (pin "4") (pinfunction "C_4") (pintype "passive"))
      (node (ref "U5") (pin "92") (pinfunction "PB6/I2C1_SCL/TIM4_CH1/CAN2_TX/DCMI_D5/USART1_TX/EVENTOUT_92") (pintype "bidirectional"))
    )
    (net (code "16") (name "/IIC1{slash}SCL") (class "Default")
      (node (ref "JP2") (pin "3") (pinfunction "3_3") (pintype "passive"))
      (node (ref "U5") (pin "95") (pinfunction "PB8/TIM4_CH3/SDIO_D4/TIM10_CH1/DCMI_D6/ETH_MII_TXD3/I2C1_SCL/CAN1_RX/EVENTOUT_95") (pintype "bidirectional"))
    )
    (net (code "17") (name "/IIC1{slash}SDA") (class "Default")
      (node (ref "JP2") (pin "4") (pinfunction "4_4") (pintype "passive"))
      (node (ref "U5") (pin "96") (pinfunction "PB9/SPI2_NSS/I2S2_WS/TIM4_CH4/TIM11_CH1/SDIO_D5/DCMI_D7/I2C1_SDA/CAN1_TX/EVENTOUT_96") (pintype "bidirectional"))
    )
    (net (code "18") (name "/K210_RX") (class "Default")
      (node (ref "U4") (pin "4") (pinfunction "IO4_4") (pintype "passive"))
      (node (ref "U5") (pin "78") (pinfunction "PC10/SPI3_SCK/I2S3_CK/UART4_TX/SDIO_D2/DCMI_D8/USART3_TX/EVENTOUT_78") (pintype "bidirectional"))
    )
    (net (code "19") (name "/K210_TX") (class "Default")
      (node (ref "U4") (pin "5") (pinfunction "IO5_5") (pintype "passive"))
      (node (ref "U5") (pin "79") (pinfunction "PC11/UART4_RX/SPI3_MISO/SDIO_D3/DCMI_D4/USART3_RX/I2S3ext_SD/EVENTOUT_79") (pintype "bidirectional"))
    )
    (net (code "20") (name "/LED") (class "Default")
      (node (ref "LED1") (pin "2") (pinfunction "K_2") (pintype "passive"))
      (node (ref "U5") (pin "4") (pinfunction "PE5/TRACED2/FSMC_A21/TIM9_CH1/DCMI_D6/EVENTOUT_4") (pintype "bidirectional"))
    )
    (net (code "21") (name "/LEFT_KEY") (class "Default")
      (node (ref "C14") (pin "1") (pinfunction "1_1") (pintype "passive"))
      (node (ref "R11") (pin "2") (pinfunction "2_2") (pintype "passive"))
      (node (ref "S4") (pin "1") (pinfunction "1_1") (pintype "passive"))
      (node (ref "U5") (pin "98") (pinfunction "PE1/FSMC_NBL1/DCMI_D3/EVENTOUT_98") (pintype "bidirectional"))
    )
    (net (code "22") (name "/OK_KEY") (class "Default")
      (node (ref "C16") (pin "1") (pinfunction "1_1") (pintype "passive"))
      (node (ref "R13") (pin "2") (pinfunction "2_2") (pintype "passive"))
      (node (ref "S6") (pin "1") (pinfunction "1_1") (pintype "passive"))
      (node (ref "U5") (pin "2") (pinfunction "PE3/TRACED0/FSMC_A19/EVENTOUT_2") (pintype "bidirectional"))
    )
    (net (code "23") (name "/PA0") (class "Default")
      (node (ref "JP11") (pin "3") (pinfunction "3_3") (pintype "passive"))
      (node (ref "U5") (pin "23") (pinfunction "PA0-WKUP(PA0)/USART2_CTS/UART4_TX/ETH_MII_CRS/TIM2_CH1_ETR/TIM5_CH1/TIM8_ETR/EVENTOUT/ADC123_IN0/WKUP_23") (pintype "bidirectional"))
    )
    (net (code "24") (name "/PA1") (class "Default")
      (node (ref "JP12") (pin "3") (pinfunction "3_3") (pintype "passive"))
      (node (ref "U5") (pin "24") (pinfunction "PA1/USART2_RTS/UART4_RX/ETH_RMII_REF_CLK/ETH_MII_RX_CLK/TIM5_CH2/TIM2_CH2/EVENTOUT/ADC123_IN1_24") (pintype "bidirectional"))
    )
    (net (code "25") (name "/PA2") (class "Default")
      (node (ref "JP13") (pin "3") (pinfunction "3_3") (pintype "passive"))
      (node (ref "U5") (pin "25") (pinfunction "PA2/USART2_TX/TIM5_CH3/TIM9_CH1/TIM2_CH3/ETH_MDIO/EVENTOUT/ADC123_IN2_25") (pintype "bidirectional"))
    )
    (net (code "26") (name "/PA3") (class "Default")
      (node (ref "JP14") (pin "3") (pinfunction "3_3") (pintype "passive"))
      (node (ref "U5") (pin "26") (pinfunction "PA3/USART2_RX/TIM5_CH4/TIM9_CH2/TIM2_CH4/OTG_HS_ULPI_D0/ETH_MII_COL/EVENTOUT/ADC123_IN3_26") (pintype "bidirectional"))
    )
    (net (code "27") (name "/PA4") (class "Default")
      (node (ref "JP15") (pin "3") (pinfunction "3_3") (pintype "passive"))
      (node (ref "U5") (pin "29") (pinfunction "PA4/SPI1_NSS/SPI3_NSS/USART2_CK/DCMI_HSYNC/OTG_HS_SOF/I2S3_WS/EVENTOUT/ADC12_IN4/DAC1_OUT_29") (pintype "bidirectional"))
    )
    (net (code "28") (name "/PA5") (class "Default")
      (node (ref "JP16") (pin "3") (pinfunction "3_3") (pintype "passive"))
      (node (ref "U5") (pin "30") (pinfunction "PA5/SPI1_SCK/OTG_HS_ULPI_CK/TIM2_CH1_ETR/TIM8_CHIN/EVENTOUT/ADC12_IN5/DAC2_OUT_30") (pintype "bidirectional"))
    )
    (net (code "29") (name "/PA6") (class "Default")
      (node (ref "JP17") (pin "3") (pinfunction "3_3") (pintype "passive"))
      (node (ref "U5") (pin "31") (pinfunction "PA6/SPI1_MISO/TIM8_BKIN/TIM13_CH1/DCMI_PIXCLK/TIM3_CH1/TIM1_BKIN/EVENTOUT/ADC12_IN6_31") (pintype "bidirectional"))
    )
    (net (code "30") (name "/PA7") (class "Default")
      (node (ref "JP18") (pin "3") (pinfunction "3_3") (pintype "passive"))
      (node (ref "U5") (pin "32") (pinfunction "PA7/SPI1_MOSI/TIM8_CH1N/TIM14_CH1/TIM3_CH2/ETH_MII_RX_DV/TIM1_CH1N/RMII_CRS_DV/EVENTOUT/ADC12_IN7_32") (pintype "bidirectional"))
    )
    (net (code "31") (name "/PA9") (class "Default")
      (node (ref "U3") (pin "3") (pinfunction "RXD_3") (pintype "passive"))
      (node (ref "U5") (pin "68") (pinfunction "PA9/USART1_TX/TIM1_CH2/I2C3_SMBA/DCMI_D0/EVENTOUT/OTG_FS_VBUS_68") (pintype "bidirectional"))
    )
    (net (code "32") (name "/PA10") (class "Default")
      (node (ref "U3") (pin "2") (pinfunction "TXD_2") (pintype "passive"))
      (node (ref "U5") (pin "69") (pinfunction "PA10/USART1_RX/TIM1_CH3/OTG_FS_ID/DCMI_D1/EVENTOUT_69") (pintype "bidirectional"))
    )
    (net (code "33") (name "/PB0") (class "Default")
      (node (ref "JP21") (pin "3") (pinfunction "3_3") (pintype "passive"))
      (node (ref "U5") (pin "35") (pinfunction "PB0/TIM3_CH3/TIM8_CH2N/OTG_HS_ULPI_D1/ETH_MII_RXD2/TIM1_CH2N/EVENTOUT/ADC12_IN8_35") (pintype "bidirectional"))
    )
    (net (code "34") (name "/PB1") (class "Default")
      (node (ref "JP22") (pin "3") (pinfunction "3_3") (pintype "passive"))
      (node (ref "U5") (pin "36") (pinfunction "PB1/TIM3_CH4/TIM8_CH3N/OTG_HS_ULPI_D2/ETH_MII_RXD3/OTG_HS_INTN/TIM1_CH3N/EVENTOUT/ADC12_IN9_36") (pintype "bidirectional"))
    )
    (net (code "35") (name "/PB10") (class "Default")
      (node (ref "JP10") (pin "2") (pinfunction "2_2") (pintype "passive"))
      (node (ref "U5") (pin "47") (pinfunction "PB10/SPI2_SCK/I2S2_CK/I2C2_SCL/USART3_TX/OTG_HS_ULPI_D3/ETH_MII_RX_ER/TIM2_CH3/EVENTOUT_47") (pintype "bidirectional"))
    )
    (net (code "36") (name "/PB11") (class "Default")
      (node (ref "JP10") (pin "3") (pinfunction "3_3") (pintype "passive"))
      (node (ref "U5") (pin "48") (pinfunction "PB11/I2C2_SDA/USART3_RX/OTG_HS_ULPI_D4/ETH_RMII_TX_EN/ETH_MII_TX_EN/TIM2_CH4/EVENTOUT_48") (pintype "bidirectional"))
    )
    (net (code "37") (name "/PC0") (class "Default")
      (node (ref "JP6") (pin "3") (pinfunction "3_3") (pintype "passive"))
      (node (ref "U5") (pin "15") (pinfunction "PC0/OTG_HS_ULPI_STP/EVENTOUT/ADC123_IN10_15") (pintype "bidirectional"))
    )
    (net (code "38") (name "/PC1") (class "Default")
      (node (ref "JP7") (pin "3") (pinfunction "3_3") (pintype "passive"))
      (node (ref "U5") (pin "16") (pinfunction "PC1/ETH_MDC/EVENTOUT/ADC123_IN11_16") (pintype "bidirectional"))
    )
    (net (code "39") (name "/PC2") (class "Default")
      (node (ref "JP8") (pin "3") (pinfunction "3_3") (pintype "passive"))
      (node (ref "U5") (pin "17") (pinfunction "PC2/SPI2_MISO/OTG_HS_ULPI_DIR/TH_MII_TXD2/I2S2ext_SD/EVENTOUT/ADC123_IN12_17") (pintype "bidirectional"))
    )
    (net (code "40") (name "/PC3") (class "Default")
      (node (ref "JP9") (pin "3") (pinfunction "3_3") (pintype "passive"))
      (node (ref "U5") (pin "18") (pinfunction "PC3/SPI2_MOSI/I2S2_SD/OTG_HS_ULPI_NXT/ETH_MII_TX_CLK/EVENTOUT/ADC123_IN13_18") (pintype "bidirectional"))
    )
    (net (code "41") (name "/PC4") (class "Default")
      (node (ref "JP19") (pin "3") (pinfunction "3_3") (pintype "passive"))
      (node (ref "U5") (pin "33") (pinfunction "PC4/ETH_RMII_RX_D0/ETH_MII_RX_D0/EVENTOUT/ADC12_IN14_33") (pintype "bidirectional"))
    )
    (net (code "42") (name "/PC5") (class "Default")
      (node (ref "JP20") (pin "3") (pinfunction "3_3") (pintype "passive"))
      (node (ref "U5") (pin "34") (pinfunction "PC5/ETH_RMII_RX_D1/ETH_MII_RX_D1/EVENTOUT/ADC12_IN15_34") (pintype "bidirectional"))
    )
    (net (code "43") (name "/PC6") (class "Default")
      (node (ref "R24") (pin "1") (pinfunction "1_1") (pintype "passive"))
      (node (ref "U5") (pin "63") (pinfunction "PC6/I2S2_MCK/TIM8_CH1/SDIO_D6/USART6_TX/DCMI_D0/TIM3_CH1/EVENTOUT_63") (pintype "bidirectional"))
    )
    (net (code "44") (name "/PC7") (class "Default")
      (node (ref "R20") (pin "1") (pinfunction "1_1") (pintype "passive"))
      (node (ref "U5") (pin "64") (pinfunction "PC7/I2S3_MCK/TIM8_CH2/SDIO_D7/USART6_RX/DCMI_D1/TIM3_CH2/EVENTOUT_64") (pintype "bidirectional"))
    )
    (net (code "45") (name "/PC8") (class "Default")
      (node (ref "R34") (pin "1") (pinfunction "1_1") (pintype "passive"))
      (node (ref "U5") (pin "65") (pinfunction "PC8/TIM8_CH3/SDIO_D0/TIM3_CH3/USART6_CK/DCMI_D2/EVENTOUT_65") (pintype "bidirectional"))
    )
    (net (code "46") (name "/PC9") (class "Default")
      (node (ref "R30") (pin "1") (pinfunction "1_1") (pintype "passive"))
      (node (ref "U5") (pin "66") (pinfunction "PC9/I2S_CKIN/MCO2/TIM8_CH4/SDIO_D1//I2C3_SDA/DCMI_D3/TIM3_CH4/EVENTOUT_66") (pintype "bidirectional"))
    )
    (net (code "47") (name "/PWMOL1") (class "Default")
      (node (ref "JP27") (pin "3") (pinfunction "3_3") (pintype "passive"))
      (node (ref "R18") (pin "2") (pinfunction "2_2") (pintype "passive"))
      (node (ref "U6") (pin "4") (pinfunction "C_4") (pintype "passive"))
    )
    (net (code "48") (name "/PWMOL2") (class "Default")
      (node (ref "JP27") (pin "2") (pinfunction "2_2") (pintype "passive"))
      (node (ref "R22") (pin "2") (pinfunction "2_2") (pintype "passive"))
      (node (ref "U8") (pin "4") (pinfunction "C_4") (pintype "passive"))
    )
    (net (code "49") (name "/PWMOR1") (class "Default")
      (node (ref "JP30") (pin "3") (pinfunction "3_3") (pintype "passive"))
      (node (ref "R26") (pin "2") (pinfunction "2_2") (pintype "passive"))
      (node (ref "U10") (pin "4") (pinfunction "C_4") (pintype "passive"))
    )
    (net (code "50") (name "/PWMOR2") (class "Default")
      (node (ref "JP30") (pin "2") (pinfunction "2_2") (pintype "passive"))
      (node (ref "R32") (pin "2") (pinfunction "2_2") (pintype "passive"))
      (node (ref "U12") (pin "4") (pinfunction "C_4") (pintype "passive"))
    )
    (net (code "51") (name "/RIGHT_KEY") (class "Default")
      (node (ref "C15") (pin "1") (pinfunction "1_1") (pintype "passive"))
      (node (ref "R12") (pin "2") (pinfunction "2_2") (pintype "passive"))
      (node (ref "S5") (pin "1") (pinfunction "1_1") (pintype "passive"))
      (node (ref "U5") (pin "1") (pinfunction "PE2/TRACECLK/FSMC_A23/ETH_MII_TXD3/EVENTOUT_1") (pintype "bidirectional"))
    )
    (net (code "52") (name "/RST") (class "Default")
      (node (ref "C21") (pin "1") (pinfunction "1_1") (pintype "passive"))
      (node (ref "LED4") (pin "2") (pinfunction "K_2") (pintype "passive"))
      (node (ref "R16") (pin "2") (pinfunction "2_2") (pintype "passive"))
      (node (ref "S9") (pin "1") (pinfunction "1_1") (pintype "passive"))
      (node (ref "U5") (pin "14") (pinfunction "NRST_14") (pintype "bidirectional"))
    )
    (net (code "53") (name "/SWCLK") (class "Default")
      (node (ref "JP1") (pin "3") (pinfunction "SWCLK_3") (pintype "passive"))
      (node (ref "U5") (pin "76") (pinfunction "PA14(JTCK-SWCLK)/JTCK-SWCLK/EVENTOUT_76") (pintype "bidirectional"))
      (node (ref "USB1") (pin "A6") (pinfunction "D+_A6") (pintype "passive"))
      (node (ref "USB1") (pin "B6") (pinfunction "D+_B6") (pintype "passive"))
    )
    (net (code "54") (name "/SWDIO") (class "Default")
      (node (ref "JP1") (pin "2") (pinfunction "SWDIO_2") (pintype "passive"))
      (node (ref "U5") (pin "72") (pinfunction "PA13(JTMS-SWDIO)/JTMS-SWDIO/EVENTOUT_72") (pintype "bidirectional"))
      (node (ref "USB1") (pin "A7") (pinfunction "D-_A7") (pintype "passive"))
      (node (ref "USB1") (pin "B7") (pinfunction "D-_B7") (pintype "passive"))
    )
    (net (code "55") (name "/UP_KEY") (class "Default")
      (node (ref "C12") (pin "1") (pinfunction "1_1") (pintype "passive"))
      (node (ref "R9") (pin "2") (pinfunction "2_2") (pintype "passive"))
      (node (ref "S2") (pin "1") (pinfunction "1_1") (pintype "passive"))
      (node (ref "U5") (pin "97") (pinfunction "PE0/TIM4_ETR/FSMC_NBL0/DCMI_D2/EVENTOUT_97") (pintype "bidirectional"))
    )
    (net (code "56") (name "/VDDA") (class "Default")
      (node (ref "C22") (pin "1") (pinfunction "1_1") (pintype "passive"))
      (node (ref "C28") (pin "1") (pinfunction "1_1") (pintype "passive"))
      (node (ref "R28") (pin "2") (pinfunction "2_2") (pintype "passive"))
      (node (ref "U5") (pin "21") (pinfunction "VREF+_21") (pintype "power_in"))
      (node (ref "U5") (pin "22") (pinfunction "VDDA_22") (pintype "power_in"))
    )
    (net (code "57") (name "/motorL+") (class "Default")
      (node (ref "JP25") (pin "1") (pinfunction "1_1") (pintype "passive"))
      (node (ref "JP26") (pin "1") (pinfunction "1_1") (pintype "passive"))
      (node (ref "S7") (pin "2") (pinfunction "2_2") (pintype "passive"))
      (node (ref "S7") (pin "3") (pinfunction "3_3") (pintype "passive"))
    )
    (net (code "58") (name "/motorL-") (class "Default")
      (node (ref "JP24") (pin "2") (pinfunction "2_2") (pintype "passive"))
      (node (ref "JP25") (pin "6") (pinfunction "6_6") (pintype "passive"))
      (node (ref "JP26") (pin "6") (pinfunction "6_6") (pintype "passive"))
    )
    (net (code "59") (name "/motorR+") (class "Default")
      (node (ref "JP29") (pin "1") (pinfunction "1_1") (pintype "passive"))
      (node (ref "JP31") (pin "1") (pinfunction "1_1") (pintype "passive"))
      (node (ref "JP32") (pin "1") (pinfunction "1_1") (pintype "passive"))
    )
    (net (code "60") (name "/motorR-") (class "Default")
      (node (ref "JP31") (pin "6") (pinfunction "6_6") (pintype "passive"))
      (node (ref "JP32") (pin "6") (pinfunction "6_6") (pintype "passive"))
      (node (ref "S8") (pin "2") (pinfunction "2_2") (pintype "passive"))
      (node (ref "S8") (pin "3") (pinfunction "3_3") (pintype "passive"))
    )
    (net (code "61") (name "3.3V") (class "Default")
      (node (ref "C23") (pin "2") (pinfunction "2_2") (pintype "passive"))
      (node (ref "C24") (pin "2") (pinfunction "2_2") (pintype "passive"))
      (node (ref "C25") (pin "2") (pinfunction "2_2") (pintype "passive"))
      (node (ref "C26") (pin "2") (pinfunction "2_2") (pintype "passive"))
      (node (ref "C27") (pin "2") (pinfunction "2_2") (pintype "passive"))
      (node (ref "F2") (pin "2") (pinfunction "2_2") (pintype "passive"))
      (node (ref "JP1") (pin "1") (pinfunction "VCC_1") (pintype "passive"))
      (node (ref "R1") (pin "1") (pinfunction "1_1") (pintype "passive"))
      (node (ref "R10") (pin "1") (pinfunction "1_1") (pintype "passive"))
      (node (ref "R11") (pin "1") (pinfunction "1_1") (pintype "passive"))
      (node (ref "R12") (pin "1") (pinfunction "1_1") (pintype "passive"))
      (node (ref "R13") (pin "1") (pinfunction "1_1") (pintype "passive"))
      (node (ref "R16") (pin "1") (pinfunction "1_1") (pintype "passive"))
      (node (ref "R17") (pin "1") (pinfunction "1_1") (pintype "passive"))
      (node (ref "R19") (pin "1") (pinfunction "1_1") (pintype "passive"))
      (node (ref "R23") (pin "1") (pinfunction "1_1") (pintype "passive"))
      (node (ref "R27") (pin "1") (pinfunction "1_1") (pintype "passive"))
      (node (ref "R28") (pin "1") (pinfunction "1_1") (pintype "passive"))
      (node (ref "R3") (pin "2") (pinfunction "2_2") (pintype "passive"))
      (node (ref "R33") (pin "1") (pinfunction "1_1") (pintype "passive"))
      (node (ref "R9") (pin "1") (pinfunction "1_1") (pintype "passive"))
      (node (ref "U10") (pin "1") (pinfunction "A_1") (pintype "passive"))
      (node (ref "U12") (pin "1") (pinfunction "A_1") (pintype "passive"))
      (node (ref "U5") (pin "100") (pinfunction "VDD_100") (pintype "power_in"))
      (node (ref "U5") (pin "11") (pinfunction "VDD_11") (pintype "power_in"))
      (node (ref "U5") (pin "19") (pinfunction "VDD_19") (pintype "power_in"))
      (node (ref "U5") (pin "28") (pinfunction "VDD_28") (pintype "power_in"))
      (node (ref "U5") (pin "50") (pinfunction "VDD_50") (pintype "power_in"))
      (node (ref "U5") (pin "75") (pinfunction "VDD_75") (pintype "power_in"))
      (node (ref "U6") (pin "1") (pinfunction "A_1") (pintype "passive"))
      (node (ref "U8") (pin "1") (pinfunction "A_1") (pintype "passive"))
      (node (ref "USB1") (pin "A4") (pinfunction "VBUS_A4") (pintype "passive"))
      (node (ref "USB1") (pin "A9") (pinfunction "VBUS_A9") (pintype "passive"))
      (node (ref "USB1") (pin "B4") (pinfunction "VBUS_B4") (pintype "passive"))
      (node (ref "USB1") (pin "B9") (pinfunction "VBUS_B9") (pintype "passive"))
    )
    (net (code "62") (name "5V") (class "Default")
      (node (ref "C10") (pin "2") (pinfunction "2_2") (pintype "passive"))
      (node (ref "C11") (pin "2") (pinfunction "2_2") (pintype "passive"))
      (node (ref "C4") (pin "1") (pinfunction "A_1") (pintype "passive"))
      (node (ref "C5") (pin "2") (pinfunction "2_2") (pintype "passive"))
      (node (ref "C6") (pin "1") (pinfunction "1_1") (pintype "passive"))
      (node (ref "C8") (pin "2") (pinfunction "2_2") (pintype "passive"))
      (node (ref "C9") (pin "2") (pinfunction "2_2") (pintype "passive"))
      (node (ref "F1") (pin "2") (pinfunction "2_2") (pintype "passive"))
      (node (ref "F3") (pin "1") (pinfunction "1_1") (pintype "passive"))
      (node (ref "JP10") (pin "5") (pinfunction "5_5") (pintype "passive"))
      (node (ref "JP11") (pin "1") (pinfunction "1_1") (pintype "passive"))
      (node (ref "JP12") (pin "1") (pinfunction "1_1") (pintype "passive"))
      (node (ref "JP13") (pin "1") (pinfunction "1_1") (pintype "passive"))
      (node (ref "JP14") (pin "1") (pinfunction "1_1") (pintype "passive"))
      (node (ref "JP15") (pin "1") (pinfunction "1_1") (pintype "passive"))
      (node (ref "JP16") (pin "1") (pinfunction "1_1") (pintype "passive"))
      (node (ref "JP17") (pin "1") (pinfunction "1_1") (pintype "passive"))
      (node (ref "JP18") (pin "1") (pinfunction "1_1") (pintype "passive"))
      (node (ref "JP19") (pin "1") (pinfunction "1_1") (pintype "passive"))
      (node (ref "JP2") (pin "1") (pinfunction "1_1") (pintype "passive"))
      (node (ref "JP20") (pin "1") (pinfunction "1_1") (pintype "passive"))
      (node (ref "JP21") (pin "1") (pinfunction "1_1") (pintype "passive"))
      (node (ref "JP22") (pin "1") (pinfunction "1_1") (pintype "passive"))
      (node (ref "JP25") (pin "4") (pinfunction "4_4") (pintype "passive"))
      (node (ref "JP3") (pin "1") (pinfunction "1_1") (pintype "passive"))
      (node (ref "JP31") (pin "4") (pinfunction "4_4") (pintype "passive"))
      (node (ref "JP4") (pin "1") (pinfunction "1_1") (pintype "passive"))
      (node (ref "JP6") (pin "1") (pinfunction "1_1") (pintype "passive"))
      (node (ref "JP7") (pin "1") (pinfunction "1_1") (pintype "passive"))
      (node (ref "JP8") (pin "1") (pinfunction "1_1") (pintype "passive"))
      (node (ref "JP9") (pin "1") (pinfunction "1_1") (pintype "passive"))
      (node (ref "L1") (pin "2") (pinfunction "2_2") (pintype "passive"))
      (node (ref "R18") (pin "1") (pinfunction "1_1") (pintype "passive"))
      (node (ref "R2") (pin "2") (pinfunction "2_2") (pintype "passive"))
      (node (ref "R22") (pin "1") (pinfunction "1_1") (pintype "passive"))
      (node (ref "R26") (pin "1") (pinfunction "1_1") (pintype "passive"))
      (node (ref "R32") (pin "1") (pinfunction "1_1") (pintype "passive"))
      (node (ref "U1") (pin "4") (pinfunction "FB_4") (pintype "input"))
      (node (ref "U11") (pin "1") (pinfunction "A_1") (pintype "passive"))
      (node (ref "U13") (pin "1") (pinfunction "A_1") (pintype "passive"))
      (node (ref "U2") (pin "3") (pinfunction "Vin_3") (pintype "passive"))
      (node (ref "U3") (pin "16") (pinfunction "VCC_16") (pintype "passive"))
      (node (ref "U7") (pin "1") (pinfunction "A_1") (pintype "passive"))
      (node (ref "U9") (pin "1") (pinfunction "A_1") (pintype "passive"))
    )
    (net (code "63") (name "24V") (class "Default")
      (node (ref "C1") (pin "2") (pinfunction "2_2") (pintype "passive"))
      (node (ref "C7") (pin "1") (pinfunction "A_1") (pintype "passive"))
      (node (ref "D2") (pin "2") (pinfunction "2_2") (pintype "passive"))
      (node (ref "D3") (pin "1") (pinfunction "A_1") (pintype "passive"))
      (node (ref "D4") (pin "1") (pinfunction "A_1") (pintype "passive"))
      (node (ref "JP5") (pin "2") (pinfunction "2_2") (pintype "passive"))
      (node (ref "U1") (pin "1") (pinfunction "IN_1") (pintype "power_in"))
    )
    (net (code "64") (name "GGND") (class "Default")
      (node (ref "D2") (pin "1") (pinfunction "1_1") (pintype "passive"))
      (node (ref "JP23") (pin "2") (pinfunction "2_2") (pintype "passive"))
      (node (ref "JP25") (pin "3") (pinfunction "3_3") (pintype "passive"))
      (node (ref "JP27") (pin "1") (pinfunction "1_1") (pintype "passive"))
      (node (ref "JP27") (pin "4") (pinfunction "4_4") (pintype "passive"))
      (node (ref "JP27") (pin "5") (pinfunction "5_5") (pintype "passive"))
      (node (ref "JP28") (pin "1") (pinfunction "1_1") (pintype "passive"))
      (node (ref "JP30") (pin "1") (pinfunction "1_1") (pintype "passive"))
      (node (ref "JP30") (pin "4") (pinfunction "4_4") (pintype "passive"))
      (node (ref "JP30") (pin "5") (pinfunction "5_5") (pintype "passive"))
      (node (ref "JP31") (pin "3") (pinfunction "3_3") (pintype "passive"))
      (node (ref "JP5") (pin "1") (pinfunction "1_1") (pintype "passive"))
      (node (ref "R6") (pin "2") (pinfunction "2_2") (pintype "passive"))
      (node (ref "U10") (pin "3") (pinfunction "E_3") (pintype "passive"))
      (node (ref "U12") (pin "3") (pinfunction "E_3") (pintype "passive"))
      (node (ref "U6") (pin "3") (pinfunction "E_3") (pintype "passive"))
      (node (ref "U8") (pin "3") (pinfunction "E_3") (pintype "passive"))
    )
    (net (code "65") (name "GND") (class "Default")
      (node (ref "C10") (pin "1") (pinfunction "1_1") (pintype "passive"))
      (node (ref "C11") (pin "1") (pinfunction "1_1") (pintype "passive"))
      (node (ref "C12") (pin "2") (pinfunction "2_2") (pintype "passive"))
      (node (ref "C13") (pin "2") (pinfunction "2_2") (pintype "passive"))
      (node (ref "C14") (pin "2") (pinfunction "2_2") (pintype "passive"))
      (node (ref "C15") (pin "2") (pinfunction "2_2") (pintype "passive"))
      (node (ref "C16") (pin "2") (pinfunction "2_2") (pintype "passive"))
      (node (ref "C17") (pin "2") (pinfunction "2_2") (pintype "passive"))
      (node (ref "C18") (pin "1") (pinfunction "1_1") (pintype "passive"))
      (node (ref "C19") (pin "2") (pinfunction "2_2") (pintype "passive"))
      (node (ref "C2") (pin "2") (pinfunction "2_2") (pintype "passive"))
      (node (ref "C20") (pin "1") (pinfunction "1_1") (pintype "passive"))
      (node (ref "C21") (pin "2") (pinfunction "2_2") (pintype "passive"))
      (node (ref "C23") (pin "1") (pinfunction "1_1") (pintype "passive"))
      (node (ref "C24") (pin "1") (pinfunction "1_1") (pintype "passive"))
      (node (ref "C25") (pin "1") (pinfunction "1_1") (pintype "passive"))
      (node (ref "C26") (pin "1") (pinfunction "1_1") (pintype "passive"))
      (node (ref "C27") (pin "1") (pinfunction "1_1") (pintype "passive"))
      (node (ref "C3") (pin "2") (pinfunction "K_2") (pintype "passive"))
      (node (ref "C4") (pin "2") (pinfunction "K_2") (pintype "passive"))
      (node (ref "C5") (pin "1") (pinfunction "1_1") (pintype "passive"))
      (node (ref "C6") (pin "2") (pinfunction "2_2") (pintype "passive"))
      (node (ref "C7") (pin "2") (pinfunction "K_2") (pintype "passive"))
      (node (ref "C8") (pin "1") (pinfunction "1_1") (pintype "passive"))
      (node (ref "C9") (pin "1") (pinfunction "1_1") (pintype "passive"))
      (node (ref "D1") (pin "1") (pinfunction "A_1") (pintype "passive"))
      (node (ref "JP1") (pin "4") (pinfunction "GND_4") (pintype "passive"))
      (node (ref "JP10") (pin "4") (pinfunction "4_4") (pintype "passive"))
      (node (ref "JP11") (pin "2") (pinfunction "2_2") (pintype "passive"))
      (node (ref "JP12") (pin "2") (pinfunction "2_2") (pintype "passive"))
      (node (ref "JP13") (pin "2") (pinfunction "2_2") (pintype "passive"))
      (node (ref "JP14") (pin "2") (pinfunction "2_2") (pintype "passive"))
      (node (ref "JP15") (pin "2") (pinfunction "2_2") (pintype "passive"))
      (node (ref "JP16") (pin "2") (pinfunction "2_2") (pintype "passive"))
      (node (ref "JP17") (pin "2") (pinfunction "2_2") (pintype "passive"))
      (node (ref "JP18") (pin "2") (pinfunction "2_2") (pintype "passive"))
      (node (ref "JP19") (pin "2") (pinfunction "2_2") (pintype "passive"))
      (node (ref "JP2") (pin "2") (pinfunction "2_2") (pintype "passive"))
      (node (ref "JP20") (pin "2") (pinfunction "2_2") (pintype "passive"))
      (node (ref "JP21") (pin "2") (pinfunction "2_2") (pintype "passive"))
      (node (ref "JP22") (pin "2") (pinfunction "2_2") (pintype "passive"))
      (node (ref "JP3") (pin "3") (pinfunction "3_3") (pintype "passive"))
      (node (ref "JP4") (pin "3") (pinfunction "3_3") (pintype "passive"))
      (node (ref "JP6") (pin "2") (pinfunction "2_2") (pintype "passive"))
      (node (ref "JP7") (pin "2") (pinfunction "2_2") (pintype "passive"))
      (node (ref "JP8") (pin "2") (pinfunction "2_2") (pintype "passive"))
      (node (ref "JP9") (pin "2") (pinfunction "2_2") (pintype "passive"))
      (node (ref "LED2") (pin "2") (pinfunction "K_2") (pintype "passive"))
      (node (ref "LED3") (pin "2") (pinfunction "K_2") (pintype "passive"))
      (node (ref "R14") (pin "1") (pinfunction "1_1") (pintype "passive"))
      (node (ref "R15") (pin "1") (pinfunction "1_1") (pintype "passive"))
      (node (ref "R29") (pin "2") (pinfunction "2_2") (pintype "passive"))
      (node (ref "R5") (pin "1") (pinfunction "1_1") (pintype "passive"))
      (node (ref "R6") (pin "1") (pinfunction "1_1") (pintype "passive"))
      (node (ref "R7") (pin "1") (pintype "passive"))
      (node (ref "R8") (pin "2") (pintype "passive"))
      (node (ref "S2") (pin "2") (pinfunction "2_2") (pintype "passive"))
      (node (ref "S3") (pin "2") (pinfunction "2_2") (pintype "passive"))
      (node (ref "S4") (pin "2") (pinfunction "2_2") (pintype "passive"))
      (node (ref "S5") (pin "2") (pinfunction "2_2") (pintype "passive"))
      (node (ref "S6") (pin "2") (pinfunction "2_2") (pintype "passive"))
      (node (ref "S9") (pin "2") (pinfunction "2_2") (pintype "passive"))
      (node (ref "U1") (pin "3") (pinfunction "GND_3") (pintype "power_in"))
      (node (ref "U11") (pin "3") (pinfunction "E_3") (pintype "passive"))
      (node (ref "U13") (pin "3") (pinfunction "E_3") (pintype "passive"))
      (node (ref "U2") (pin "1") (pinfunction "GND_1") (pintype "passive"))
      (node (ref "U3") (pin "1") (pinfunction "GND_1") (pintype "passive"))
      (node (ref "U4") (pin "GND") (pinfunction "GND_GND") (pintype "passive"))
      (node (ref "U5") (pin "10") (pinfunction "VSS_10") (pintype "power_in"))
      (node (ref "U5") (pin "27") (pinfunction "VSS_27") (pintype "power_in"))
      (node (ref "U5") (pin "74") (pinfunction "VSS_74") (pintype "power_in"))
      (node (ref "U5") (pin "99") (pinfunction "VSS_99") (pintype "power_in"))
      (node (ref "U7") (pin "3") (pinfunction "E_3") (pintype "passive"))
      (node (ref "U9") (pin "3") (pinfunction "E_3") (pintype "passive"))
      (node (ref "USB1") (pin "1") (pinfunction "SH1_1") (pintype "passive"))
      (node (ref "USB1") (pin "2") (pinfunction "SH2_2") (pintype "passive"))
      (node (ref "USB1") (pin "3") (pinfunction "SH3_3") (pintype "passive"))
      (node (ref "USB1") (pin "4") (pinfunction "SH4_4") (pintype "passive"))
      (node (ref "USB2") (pin "1") (pinfunction "SH1_1") (pintype "passive"))
      (node (ref "USB2") (pin "2") (pinfunction "SH2_2") (pintype "passive"))
      (node (ref "USB2") (pin "3") (pinfunction "SH3_3") (pintype "passive"))
      (node (ref "USB2") (pin "4") (pinfunction "SH4_4") (pintype "passive"))
      (node (ref "USB2") (pin "A1") (pinfunction "GND_A1") (pintype "passive"))
      (node (ref "USB2") (pin "A12") (pinfunction "GND_A12") (pintype "passive"))
      (node (ref "USB2") (pin "B1") (pinfunction "GND_B1") (pintype "passive"))
      (node (ref "USB2") (pin "B12") (pinfunction "GND_B12") (pintype "passive"))
      (node (ref "Y1") (pin "2") (pinfunction "GND_2") (pintype "passive"))
      (node (ref "Y1") (pin "4") (pinfunction "GND_4") (pintype "passive"))
    )
    (net (code "66") (name "K210_5V") (class "Default")
      (node (ref "F3") (pin "2") (pinfunction "2_2") (pintype "passive"))
      (node (ref "U4") (pin "5V") (pinfunction "5V_5V") (pintype "passive"))
    )
    (net (code "67") (name "Net-(C1-Pad1)") (class "Default")
      (node (ref "C1") (pin "1") (pinfunction "1_1") (pintype "passive"))
      (node (ref "R4") (pin "2") (pinfunction "2_2") (pintype "passive"))
      (node (ref "S1") (pin "3") (pinfunction "3_3") (pintype "passive"))
    )
    (net (code "68") (name "Net-(C3-A)") (class "Default")
      (node (ref "C3") (pin "1") (pinfunction "A_1") (pintype "passive"))
      (node (ref "F2") (pin "1") (pinfunction "1_1") (pintype "passive"))
      (node (ref "U2") (pin "2") (pinfunction "Vout_2") (pintype "passive"))
    )
    (net (code "69") (name "Net-(D1-K)") (class "Default")
      (node (ref "D1") (pin "2") (pinfunction "K_2") (pintype "passive"))
      (node (ref "L1") (pin "1") (pinfunction "1_1") (pintype "passive"))
      (node (ref "U1") (pin "2") (pinfunction "OUT_2") (pintype "power_in"))
    )
    (net (code "70") (name "Net-(D3-K)") (class "Default")
      (node (ref "D3") (pin "2") (pinfunction "K_2") (pintype "passive"))
      (node (ref "JP23") (pin "1") (pinfunction "1_1") (pintype "passive"))
    )
    (net (code "71") (name "Net-(D4-K)") (class "Default")
      (node (ref "D4") (pin "2") (pinfunction "K_2") (pintype "passive"))
      (node (ref "JP28") (pin "2") (pinfunction "2_2") (pintype "passive"))
    )
    (net (code "72") (name "Net-(JP24-Pad1)") (class "Default")
      (node (ref "JP24") (pin "1") (pinfunction "1_1") (pintype "passive"))
      (node (ref "S7") (pin "1") (pinfunction "1_1") (pintype "passive"))
    )
    (net (code "73") (name "Net-(JP29-Pad2)") (class "Default")
      (node (ref "JP29") (pin "2") (pinfunction "2_2") (pintype "passive"))
      (node (ref "S8") (pin "1") (pinfunction "1_1") (pintype "passive"))
    )
    (net (code "74") (name "Net-(LED1-A)") (class "Default")
      (node (ref "LED1") (pin "1") (pinfunction "A_1") (pintype "passive"))
      (node (ref "R1") (pin "2") (pinfunction "2_2") (pintype "passive"))
    )
    (net (code "75") (name "Net-(LED2-A)") (class "Default")
      (node (ref "LED2") (pin "1") (pinfunction "A_1") (pintype "passive"))
      (node (ref "R2") (pin "1") (pinfunction "1_1") (pintype "passive"))
    )
    (net (code "76") (name "Net-(LED3-A)") (class "Default")
      (node (ref "LED3") (pin "1") (pinfunction "A_1") (pintype "passive"))
      (node (ref "R3") (pin "1") (pinfunction "1_1") (pintype "passive"))
    )
    (net (code "77") (name "Net-(LED4-A)") (class "Default")
      (node (ref "LED4") (pin "1") (pinfunction "A_1") (pintype "passive"))
      (node (ref "R17") (pin "2") (pinfunction "2_2") (pintype "passive"))
    )
    (net (code "78") (name "Net-(R5-Pad2)") (class "Default")
      (node (ref "R5") (pin "2") (pinfunction "2_2") (pintype "passive"))
      (node (ref "S1") (pin "2") (pinfunction "2_2") (pintype "passive"))
    )
    (net (code "79") (name "Net-(U1-~{ON}{slash}OFF)") (class "Default")
      (node (ref "R4") (pin "1") (pinfunction "1_1") (pintype "passive"))
      (node (ref "U1") (pin "5") (pinfunction "~{ON}/OFF_5") (pintype "input"))
    )
    (net (code "80") (name "Net-(U3-V3)") (class "Default")
      (node (ref "C2") (pin "1") (pinfunction "1_1") (pintype "passive"))
      (node (ref "U3") (pin "4") (pinfunction "V3_4") (pintype "passive"))
    )
    (net (code "81") (name "Net-(U5D-PH0-OSC_IN(PH0){slash}EVENTOUT{slash}OSC_IN)") (class "Default")
      (node (ref "C17") (pin "1") (pinfunction "1_1") (pintype "passive"))
      (node (ref "U5") (pin "12") (pinfunction "PH0-OSC_IN(PH0)/EVENTOUT/OSC_IN_12") (pintype "bidirectional"))
      (node (ref "Y1") (pin "3") (pinfunction "OSC2_3") (pintype "passive"))
    )
    (net (code "82") (name "Net-(U5D-PH1-OSC_OUT(PH1){slash}EVENTOUT{slash}OSC_OUT)") (class "Default")
      (node (ref "C19") (pin "1") (pinfunction "1_1") (pintype "passive"))
      (node (ref "U5") (pin "13") (pinfunction "PH1-OSC_OUT(PH1)/EVENTOUT/OSC_OUT_13") (pintype "bidirectional"))
      (node (ref "Y1") (pin "1") (pinfunction "OSC1_1") (pintype "passive"))
    )
    (net (code "83") (name "Net-(U5D-VCAP_1)") (class "Default")
      (node (ref "C18") (pin "2") (pinfunction "2_2") (pintype "passive"))
      (node (ref "U5") (pin "49") (pinfunction "VCAP_1_49") (pintype "power_in"))
    )
    (net (code "84") (name "Net-(U5D-VCAP_2)") (class "Default")
      (node (ref "C20") (pin "2") (pinfunction "2_2") (pintype "passive"))
      (node (ref "U5") (pin "73") (pinfunction "VCAP_2_73") (pintype "power_in"))
    )
    (net (code "85") (name "Net-(U5E-VSSA)") (class "Default")
      (node (ref "C22") (pin "2") (pinfunction "2_2") (pintype "passive"))
      (node (ref "C28") (pin "2") (pinfunction "2_2") (pintype "passive"))
      (node (ref "R29") (pin "1") (pinfunction "1_1") (pintype "passive"))
      (node (ref "U5") (pin "20") (pinfunction "VSSA_20") (pintype "power_in"))
    )
    (net (code "86") (name "Net-(U6-K)") (class "Default")
      (node (ref "R20") (pin "2") (pinfunction "2_2") (pintype "passive"))
      (node (ref "U6") (pin "2") (pinfunction "K_2") (pintype "passive"))
    )
    (net (code "87") (name "Net-(U7-K)") (class "Default")
      (node (ref "R21") (pin "2") (pinfunction "2_2") (pintype "passive"))
      (node (ref "U7") (pin "2") (pinfunction "K_2") (pintype "passive"))
    )
    (net (code "88") (name "Net-(U8-K)") (class "Default")
      (node (ref "R24") (pin "2") (pinfunction "2_2") (pintype "passive"))
      (node (ref "U8") (pin "2") (pinfunction "K_2") (pintype "passive"))
    )
    (net (code "89") (name "Net-(U9-K)") (class "Default")
      (node (ref "R25") (pin "2") (pinfunction "2_2") (pintype "passive"))
      (node (ref "U9") (pin "2") (pinfunction "K_2") (pintype "passive"))
    )
    (net (code "90") (name "Net-(U10-K)") (class "Default")
      (node (ref "R30") (pin "2") (pinfunction "2_2") (pintype "passive"))
      (node (ref "U10") (pin "2") (pinfunction "K_2") (pintype "passive"))
    )
    (net (code "91") (name "Net-(U11-K)") (class "Default")
      (node (ref "R31") (pin "2") (pinfunction "2_2") (pintype "passive"))
      (node (ref "U11") (pin "2") (pinfunction "K_2") (pintype "passive"))
    )
    (net (code "92") (name "Net-(U12-K)") (class "Default")
      (node (ref "R34") (pin "2") (pinfunction "2_2") (pintype "passive"))
      (node (ref "U12") (pin "2") (pinfunction "K_2") (pintype "passive"))
    )
    (net (code "93") (name "Net-(U13-K)") (class "Default")
      (node (ref "R35") (pin "2") (pinfunction "2_2") (pintype "passive"))
      (node (ref "U13") (pin "2") (pinfunction "K_2") (pintype "passive"))
    )
    (net (code "94") (name "Net-(USB2-CC1)") (class "Default")
      (node (ref "R7") (pin "2") (pintype "passive"))
      (node (ref "USB2") (pin "A5") (pinfunction "CC1_A5") (pintype "passive"))
    )
    (net (code "95") (name "Net-(USB2-CC2)") (class "Default")
      (node (ref "R8") (pin "1") (pintype "passive"))
      (node (ref "USB2") (pin "B5") (pinfunction "CC2_B5") (pintype "passive"))
    )
    (net (code "96") (name "VBUS") (class "Default")
      (node (ref "F1") (pin "1") (pinfunction "1_1") (pintype "passive"))
      (node (ref "USB2") (pin "A4") (pinfunction "VBUS_A4") (pintype "passive"))
      (node (ref "USB2") (pin "A9") (pinfunction "VBUS_A9") (pintype "passive"))
      (node (ref "USB2") (pin "B4") (pinfunction "VBUS_B4") (pintype "passive"))
      (node (ref "USB2") (pin "B9") (pinfunction "VBUS_B9") (pintype "passive"))
    )
    (net (code "97") (name "unconnected-(JP3-Pad4)") (class "Default")
      (node (ref "JP3") (pin "4") (pinfunction "4_4") (pintype "passive+no_connect"))
    )
    (net (code "98") (name "unconnected-(JP4-Pad4)") (class "Default")
      (node (ref "JP4") (pin "4") (pinfunction "4_4") (pintype "passive+no_connect"))
    )
    (net (code "99") (name "unconnected-(JP10-Pad1)") (class "Default")
      (node (ref "JP10") (pin "1") (pinfunction "1_1") (pintype "passive+no_connect"))
    )
    (net (code "100") (name "unconnected-(JP10-Pad6)") (class "Default")
      (node (ref "JP10") (pin "6") (pinfunction "6_6") (pintype "passive+no_connect"))
    )
    (net (code "101") (name "unconnected-(JP26-Pad2)") (class "Default")
      (node (ref "JP26") (pin "2") (pinfunction "2_2") (pintype "passive"))
    )
    (net (code "102") (name "unconnected-(JP26-Pad3)") (class "Default")
      (node (ref "JP26") (pin "3") (pinfunction "3_3") (pintype "passive"))
    )
    (net (code "103") (name "unconnected-(JP26-Pad4)") (class "Default")
      (node (ref "JP26") (pin "4") (pinfunction "4_4") (pintype "passive"))
    )
    (net (code "104") (name "unconnected-(JP26-Pad5)") (class "Default")
      (node (ref "JP26") (pin "5") (pinfunction "5_5") (pintype "passive"))
    )
    (net (code "105") (name "unconnected-(JP27-Pad6)") (class "Default")
      (node (ref "JP27") (pin "6") (pinfunction "6_6") (pintype "passive"))
    )
    (net (code "106") (name "unconnected-(JP30-Pad6)") (class "Default")
      (node (ref "JP30") (pin "6") (pinfunction "6_6") (pintype "passive"))
    )
    (net (code "107") (name "unconnected-(JP32-Pad2)") (class "Default")
      (node (ref "JP32") (pin "2") (pinfunction "2_2") (pintype "passive"))
    )
    (net (code "108") (name "unconnected-(JP32-Pad3)") (class "Default")
      (node (ref "JP32") (pin "3") (pinfunction "3_3") (pintype "passive"))
    )
    (net (code "109") (name "unconnected-(JP32-Pad4)") (class "Default")
      (node (ref "JP32") (pin "4") (pinfunction "4_4") (pintype "passive"))
    )
    (net (code "110") (name "unconnected-(JP32-Pad5)") (class "Default")
      (node (ref "JP32") (pin "5") (pinfunction "5_5") (pintype "passive"))
    )
    (net (code "111") (name "unconnected-(S1-Pad1)") (class "Default")
      (node (ref "S1") (pin "1") (pinfunction "1_1") (pintype "passive"))
    )
    (net (code "112") (name "unconnected-(U3-CTS#-Pad9)") (class "Default")
      (node (ref "U3") (pin "9") (pinfunction "CTS#_9") (pintype "passive+no_connect"))
    )
    (net (code "113") (name "unconnected-(U3-DCD#-Pad12)") (class "Default")
      (node (ref "U3") (pin "12") (pinfunction "DCD#_12") (pintype "passive+no_connect"))
    )
    (net (code "114") (name "unconnected-(U3-DSR#-Pad10)") (class "Default")
      (node (ref "U3") (pin "10") (pinfunction "DSR#_10") (pintype "passive+no_connect"))
    )
    (net (code "115") (name "unconnected-(U3-DTR#-Pad13)") (class "Default")
      (node (ref "U3") (pin "13") (pinfunction "DTR#_13") (pintype "passive+no_connect"))
    )
    (net (code "116") (name "unconnected-(U3-R232-Pad15)") (class "Default")
      (node (ref "U3") (pin "15") (pinfunction "R232_15") (pintype "passive+no_connect"))
    )
    (net (code "117") (name "unconnected-(U3-RI#-Pad11)") (class "Default")
      (node (ref "U3") (pin "11") (pinfunction "RI#_11") (pintype "passive+no_connect"))
    )
    (net (code "118") (name "unconnected-(U3-RTS#-Pad14)") (class "Default")
      (node (ref "U3") (pin "14") (pinfunction "RTS#_14") (pintype "passive+no_connect"))
    )
    (net (code "119") (name "unconnected-(U3-X1-Pad7)") (class "Default")
      (node (ref "U3") (pin "7") (pinfunction "X1_7") (pintype "passive+no_connect"))
    )
    (net (code "120") (name "unconnected-(U3-X2-Pad8)") (class "Default")
      (node (ref "U3") (pin "8") (pinfunction "X2_8") (pintype "passive+no_connect"))
    )
    (net (code "121") (name "unconnected-(U4-3.3V-Pad3V3)") (class "Default")
      (node (ref "U4") (pin "3V3") (pinfunction "3.3V_3V3") (pintype "passive"))
    )
    (net (code "122") (name "unconnected-(U4-IO0-Pad0)") (class "Default")
      (node (ref "U4") (pin "0") (pinfunction "IO0_0") (pintype "passive"))
    )
    (net (code "123") (name "unconnected-(U4-IO1-Pad1)") (class "Default")
      (node (ref "U4") (pin "1") (pinfunction "IO1_1") (pintype "passive"))
    )
    (net (code "124") (name "unconnected-(U4-IO2-Pad2)") (class "Default")
      (node (ref "U4") (pin "2") (pinfunction "IO2_2") (pintype "passive"))
    )
    (net (code "125") (name "unconnected-(U4-IO3-Pad3)") (class "Default")
      (node (ref "U4") (pin "3") (pinfunction "IO3_3") (pintype "passive"))
    )
    (net (code "126") (name "unconnected-(U4-IO6-Pad6)") (class "Default")
      (node (ref "U4") (pin "6") (pinfunction "IO6_6") (pintype "passive"))
    )
    (net (code "127") (name "unconnected-(U4-IO7-Pad7)") (class "Default")
      (node (ref "U4") (pin "7") (pinfunction "IO7_7") (pintype "passive"))
    )
    (net (code "128") (name "unconnected-(U4-IO8-Pad8)") (class "Default")
      (node (ref "U4") (pin "8") (pinfunction "IO8_8") (pintype "passive"))
    )
    (net (code "129") (name "unconnected-(U4-IO9-Pad9)") (class "Default")
      (node (ref "U4") (pin "9") (pinfunction "IO9_9") (pintype "passive"))
    )
    (net (code "130") (name "unconnected-(U4-IO10-Pad10)") (class "Default")
      (node (ref "U4") (pin "10") (pinfunction "IO10_10") (pintype "passive"))
    )
    (net (code "131") (name "unconnected-(U4-IO15-Pad15)") (class "Default")
      (node (ref "U4") (pin "15") (pinfunction "IO15_15") (pintype "passive"))
    )
    (net (code "132") (name "unconnected-(U4-IO16-Pad16)") (class "Default")
      (node (ref "U4") (pin "16") (pinfunction "IO16_16") (pintype "passive"))
    )
    (net (code "133") (name "unconnected-(U4-IO17-Pad17)") (class "Default")
      (node (ref "U4") (pin "17") (pinfunction "IO17_17") (pintype "passive"))
    )
    (net (code "134") (name "unconnected-(U4-IO18-Pad18)") (class "Default")
      (node (ref "U4") (pin "18") (pinfunction "IO18_18") (pintype "passive"))
    )
    (net (code "135") (name "unconnected-(U4-IO19-Pad19)") (class "Default")
      (node (ref "U4") (pin "19") (pinfunction "IO19_19") (pintype "passive"))
    )
    (net (code "136") (name "unconnected-(U4-IO20-Pad20)") (class "Default")
      (node (ref "U4") (pin "20") (pinfunction "IO20_20") (pintype "passive"))
    )
    (net (code "137") (name "unconnected-(U4-IO21-Pad21)") (class "Default")
      (node (ref "U4") (pin "21") (pinfunction "IO21_21") (pintype "passive"))
    )
    (net (code "138") (name "unconnected-(U4-IO22-Pad22)") (class "Default")
      (node (ref "U4") (pin "22") (pinfunction "IO22_22") (pintype "passive"))
    )
    (net (code "139") (name "unconnected-(U4-IO23-Pad23)") (class "Default")
      (node (ref "U4") (pin "23") (pinfunction "IO23_23") (pintype "passive"))
    )
    (net (code "140") (name "unconnected-(U4-IO24-Pad24)") (class "Default")
      (node (ref "U4") (pin "24") (pinfunction "IO24_24") (pintype "passive"))
    )
    (net (code "141") (name "unconnected-(U4-IO25-Pad25)") (class "Default")
      (node (ref "U4") (pin "25") (pinfunction "IO25_25") (pintype "passive"))
    )
    (net (code "142") (name "unconnected-(U4-IO26-Pad26)") (class "Default")
      (node (ref "U4") (pin "26") (pinfunction "IO26_26") (pintype "passive"))
    )
    (net (code "143") (name "unconnected-(U4-IO27-Pad27)") (class "Default")
      (node (ref "U4") (pin "27") (pinfunction "IO27_27") (pintype "passive"))
    )
    (net (code "144") (name "unconnected-(U4-IO28-Pad28)") (class "Default")
      (node (ref "U4") (pin "28") (pinfunction "IO28_28") (pintype "passive"))
    )
    (net (code "145") (name "unconnected-(U4-IO29-Pad29)") (class "Default")
      (node (ref "U4") (pin "29") (pinfunction "IO29_29") (pintype "passive"))
    )
    (net (code "146") (name "unconnected-(U4-IO30-Pad30)") (class "Default")
      (node (ref "U4") (pin "30") (pinfunction "IO30_30") (pintype "passive"))
    )
    (net (code "147") (name "unconnected-(U4-IO31-Pad31)") (class "Default")
      (node (ref "U4") (pin "31") (pinfunction "IO31_31") (pintype "passive"))
    )
    (net (code "148") (name "unconnected-(U4-IO32-Pad32)") (class "Default")
      (node (ref "U4") (pin "32") (pinfunction "IO32_32") (pintype "passive"))
    )
    (net (code "149") (name "unconnected-(U4-IO33-Pad33)") (class "Default")
      (node (ref "U4") (pin "33") (pinfunction "IO33_33") (pintype "passive"))
    )
    (net (code "150") (name "unconnected-(U4-IO34-Pad34)") (class "Default")
      (node (ref "U4") (pin "34") (pinfunction "IO34_34") (pintype "passive"))
    )
    (net (code "151") (name "unconnected-(U4-IO35-Pad35)") (class "Default")
      (node (ref "U4") (pin "35") (pinfunction "IO35_35") (pintype "passive"))
    )
    (net (code "152") (name "unconnected-(U4-PadRST)") (class "Default")
      (node (ref "U4") (pin "RST") (pinfunction "RST_RST") (pintype "passive"))
    )
    (net (code "153") (name "unconnected-(U5A-PA8{slash}MCO1{slash}USART1_CK{slash}TIM1_CH1{slash}I2C3_SCL{slash}OTG_FS_SOF{slash}EVENTOUT-Pad67)") (class "Default")
      (node (ref "U5") (pin "67") (pinfunction "PA8/MCO1/USART1_CK/TIM1_CH1/I2C3_SCL/OTG_FS_SOF/EVENTOUT_67") (pintype "bidirectional"))
    )
    (net (code "154") (name "unconnected-(U5A-PA11{slash}USART1_CTS{slash}CAN1_RX{slash}TIM1_CH4{slash}OTG_FS_DM{slash}EVENTOUT-Pad70)") (class "Default")
      (node (ref "U5") (pin "70") (pinfunction "PA11/USART1_CTS/CAN1_RX/TIM1_CH4/OTG_FS_DM/EVENTOUT_70") (pintype "bidirectional"))
    )
    (net (code "155") (name "unconnected-(U5A-PA12{slash}USART1_RTS{slash}CAN1_TX{slash}TIM1_ETR{slash}OTG_FS_DP{slash}EVENTOUT-Pad71)") (class "Default")
      (node (ref "U5") (pin "71") (pinfunction "PA12/USART1_RTS/CAN1_TX/TIM1_ETR/OTG_FS_DP/EVENTOUT_71") (pintype "bidirectional"))
    )
    (net (code "156") (name "unconnected-(U5A-PA15(JTDI){slash}JTDI{slash}SPI3_NSS{slash}I2S3_WS{slash}TIM2_CH1_ETR{slash}SPI1_NSS{slash}EVENTOUT-Pad77)") (class "Default")
      (node (ref "U5") (pin "77") (pinfunction "PA15(JTDI)/JTDI/SPI3_NSS/I2S3_WS/TIM2_CH1_ETR/SPI1_NSS/EVENTOUT_77") (pintype "bidirectional"))
    )
    (net (code "157") (name "unconnected-(U5A-PB3(JTDO{slash}TRACESWO){slash}JTDO{slash}TRACESWO{slash}SPI3_SCK{slash}I2S3_CK{slash}TIM2_CH2{slash}SPI1_SCK{slash}EVENTOUT-Pad89)") (class "Default")
      (node (ref "U5") (pin "89") (pinfunction "PB3(JTDO/TRACESWO)/JTDO/TRACESWO/SPI3_SCK/I2S3_CK/TIM2_CH2/SPI1_SCK/EVENTOUT_89") (pintype "bidirectional"))
    )
    (net (code "158") (name "unconnected-(U5A-PB12{slash}SPI2_NSS{slash}I2S2_WS{slash}I2C2_SMBA{slash}USART3_CK{slash}TIM1_BKIN{slash}CAN2_RX{slash}OTG_HS_ULPI_D5{slash}ETH_RMII_TXD0{slash}ETH_MII_TXD0{slash}OTG_HS_ID{slash}EVENTOUT-Pad51)") (class "Default")
      (node (ref "U5") (pin "51") (pinfunction "PB12/SPI2_NSS/I2S2_WS/I2C2_SMBA/USART3_CK/TIM1_BKIN/CAN2_RX/OTG_HS_ULPI_D5/ETH_RMII_TXD0/ETH_MII_TXD0/OTG_HS_ID/EVENTOUT_51") (pintype "bidirectional"))
    )
    (net (code "159") (name "unconnected-(U5A-PB13{slash}SPI2_SCK{slash}I2S2_CK{slash}USART3_CTS{slash}TIM1_CH1N{slash}CAN2_TX{slash}OTG_HS_ULPI_D6{slash}ETH_RMII_TXD1{slash}ETH_MII_TXD1{slash}EVENTOUT{slash}OTG_HS_VBUS-Pad52)") (class "Default")
      (node (ref "U5") (pin "52") (pinfunction "PB13/SPI2_SCK/I2S2_CK/USART3_CTS/TIM1_CH1N/CAN2_TX/OTG_HS_ULPI_D6/ETH_RMII_TXD1/ETH_MII_TXD1/EVENTOUT/OTG_HS_VBUS_52") (pintype "bidirectional"))
    )
    (net (code "160") (name "unconnected-(U5A-PB14{slash}SPI2_MISO{slash}TIM1_CH2N{slash}TIM12_CH1{slash}OTG_HS_DM{slash}USART3_RTS{slash}TIM8_CH2N{slash}I2S2ext_SD{slash}EVENTOUT-Pad53)") (class "Default")
      (node (ref "U5") (pin "53") (pinfunction "PB14/SPI2_MISO/TIM1_CH2N/TIM12_CH1/OTG_HS_DM/USART3_RTS/TIM8_CH2N/I2S2ext_SD/EVENTOUT_53") (pintype "bidirectional"))
    )
    (net (code "161") (name "unconnected-(U5A-PB15{slash}SPI2_MOSI{slash}I2S2_SD{slash}TIM1_CH3N{slash}TIM8_CH3N{slash}TIM12_CH2{slash}OTG_HS_DP{slash}EVENTOUT-Pad54)") (class "Default")
      (node (ref "U5") (pin "54") (pinfunction "PB15/SPI2_MOSI/I2S2_SD/TIM1_CH3N/TIM8_CH3N/TIM12_CH2/OTG_HS_DP/EVENTOUT_54") (pintype "bidirectional"))
    )
    (net (code "162") (name "unconnected-(U5B-PC12{slash}UART5_TX{slash}SDIO_CK{slash}DCMI_D9{slash}SPI3_MOSI{slash}I2S3_SD{slash}USART3_CK{slash}EVENTOUT-Pad80)") (class "Default")
      (node (ref "U5") (pin "80") (pinfunction "PC12/UART5_TX/SDIO_CK/DCMI_D9/SPI3_MOSI/I2S3_SD/USART3_CK/EVENTOUT_80") (pintype "bidirectional"))
    )
    (net (code "163") (name "unconnected-(U5B-PC13{slash}EVENTOUT{slash}RTC_AF1-Pad7)") (class "Default")
      (node (ref "U5") (pin "7") (pinfunction "PC13/EVENTOUT/RTC_AF1_7") (pintype "bidirectional"))
    )
    (net (code "164") (name "unconnected-(U5B-PC14-OSC32_IN(PC14){slash}EVENTOUT{slash}OSC32_IN-Pad8)") (class "Default")
      (node (ref "U5") (pin "8") (pinfunction "PC14-OSC32_IN(PC14)/EVENTOUT/OSC32_IN_8") (pintype "bidirectional"))
    )
    (net (code "165") (name "unconnected-(U5B-PC15-OSC32_OUT(PC15){slash}EVENTOUT{slash}OSC32_OUT-Pad9)") (class "Default")
      (node (ref "U5") (pin "9") (pinfunction "PC15-OSC32_OUT(PC15)/EVENTOUT/OSC32_OUT_9") (pintype "bidirectional"))
    )
    (net (code "166") (name "unconnected-(U5B-PD0{slash}FSMC_D2{slash}CAN1_RX{slash}EVENTOUT-Pad81)") (class "Default")
      (node (ref "U5") (pin "81") (pinfunction "PD0/FSMC_D2/CAN1_RX/EVENTOUT_81") (pintype "bidirectional"))
    )
    (net (code "167") (name "unconnected-(U5B-PD1{slash}FSMC_D3{slash}CAN1_TX{slash}EVENTOUT-Pad82)") (class "Default")
      (node (ref "U5") (pin "82") (pinfunction "PD1/FSMC_D3/CAN1_TX/EVENTOUT_82") (pintype "bidirectional"))
    )
    (net (code "168") (name "unconnected-(U5B-PD2{slash}TIM3_ETR{slash}UART5_RX{slash}SDIO_CMD{slash}DCMI_D11{slash}EVENTOUT-Pad83)") (class "Default")
      (node (ref "U5") (pin "83") (pinfunction "PD2/TIM3_ETR/UART5_RX/SDIO_CMD/DCMI_D11/EVENTOUT_83") (pintype "bidirectional"))
    )
    (net (code "169") (name "unconnected-(U5B-PD4{slash}FSMC_NOE{slash}USART2_RTS{slash}EVENTOUT-Pad85)") (class "Default")
      (node (ref "U5") (pin "85") (pinfunction "PD4/FSMC_NOE/USART2_RTS/EVENTOUT_85") (pintype "bidirectional"))
    )
    (net (code "170") (name "unconnected-(U5B-PD5{slash}FSMC_NWE{slash}USART2_TX{slash}EVENTOUT-Pad86)") (class "Default")
      (node (ref "U5") (pin "86") (pinfunction "PD5/FSMC_NWE/USART2_TX/EVENTOUT_86") (pintype "bidirectional"))
    )
    (net (code "171") (name "unconnected-(U5B-PD6{slash}FSMC_NWAIT{slash}USART2_RX{slash}EVENTOUT-Pad87)") (class "Default")
      (node (ref "U5") (pin "87") (pinfunction "PD6/FSMC_NWAIT/USART2_RX/EVENTOUT_87") (pintype "bidirectional"))
    )
    (net (code "172") (name "unconnected-(U5B-PD7{slash}USART2_CK{slash}FSMC_NE1{slash}FSMC_NCE2{slash}EVENTOUT-Pad88)") (class "Default")
      (node (ref "U5") (pin "88") (pinfunction "PD7/USART2_CK/FSMC_NE1/FSMC_NCE2/EVENTOUT_88") (pintype "bidirectional"))
    )
    (net (code "173") (name "unconnected-(U5B-PD8{slash}FSMC_D13{slash}USART3_TX{slash}EVENTOUT-Pad55)") (class "Default")
      (node (ref "U5") (pin "55") (pinfunction "PD8/FSMC_D13/USART3_TX/EVENTOUT_55") (pintype "bidirectional"))
    )
    (net (code "174") (name "unconnected-(U5B-PD9{slash}FSMC_D14{slash}USART3_RX{slash}EVENTOUT-Pad56)") (class "Default")
      (node (ref "U5") (pin "56") (pinfunction "PD9/FSMC_D14/USART3_RX/EVENTOUT_56") (pintype "bidirectional"))
    )
    (net (code "175") (name "unconnected-(U5B-PD10{slash}FSMC_D15{slash}USART3_CK{slash}EVENTOUT-Pad57)") (class "Default")
      (node (ref "U5") (pin "57") (pinfunction "PD10/FSMC_D15/USART3_CK/EVENTOUT_57") (pintype "bidirectional"))
    )
    (net (code "176") (name "unconnected-(U5B-PD11{slash}FSMC_CLE{slash}FSMC_A16{slash}USART3_CTS{slash}EVENTOUT-Pad58)") (class "Default")
      (node (ref "U5") (pin "58") (pinfunction "PD11/FSMC_CLE/FSMC_A16/USART3_CTS/EVENTOUT_58") (pintype "bidirectional"))
    )
    (net (code "177") (name "unconnected-(U5B-PD12{slash}FSMC_ALE{slash}FSMC_A17{slash}TIM4_CH1{slash}USART3_RTS{slash}EVENTOUT-Pad59)") (class "Default")
      (node (ref "U5") (pin "59") (pinfunction "PD12/FSMC_ALE/FSMC_A17/TIM4_CH1/USART3_RTS/EVENTOUT_59") (pintype "bidirectional"))
    )
    (net (code "178") (name "unconnected-(U5B-PD13{slash}FSMC_A18{slash}TIM4_CH2{slash}EVENTOUT-Pad60)") (class "Default")
      (node (ref "U5") (pin "60") (pinfunction "PD13/FSMC_A18/TIM4_CH2/EVENTOUT_60") (pintype "bidirectional"))
    )
    (net (code "179") (name "unconnected-(U5B-PD14{slash}FSMC_D0{slash}TIM4_CH3{slash}EVENTOUT{slash}EVENTOUT-Pad61)") (class "Default")
      (node (ref "U5") (pin "61") (pinfunction "PD14/FSMC_D0/TIM4_CH3/EVENTOUT/EVENTOUT_61") (pintype "bidirectional"))
    )
    (net (code "180") (name "unconnected-(U5C-PE6{slash}TRACED3{slash}FSMC_A22{slash}TIM9_CH2{slash}DCMI_D7{slash}EVENTOUT-Pad5)") (class "Default")
      (node (ref "U5") (pin "5") (pinfunction "PE6/TRACED3/FSMC_A22/TIM9_CH2/DCMI_D7/EVENTOUT_5") (pintype "bidirectional"))
    )
    (net (code "181") (name "unconnected-(U5C-PE7{slash}FSMC_D4{slash}TIM1_ETR{slash}EVENTOUT-Pad38)") (class "Default")
      (node (ref "U5") (pin "38") (pinfunction "PE7/FSMC_D4/TIM1_ETR/EVENTOUT_38") (pintype "bidirectional"))
    )
    (net (code "182") (name "unconnected-(U5C-PE8{slash}FSMC_D5{slash}TIM1_CH1N{slash}EVENTOUT-Pad39)") (class "Default")
      (node (ref "U5") (pin "39") (pinfunction "PE8/FSMC_D5/TIM1_CH1N/EVENTOUT_39") (pintype "bidirectional"))
    )
    (net (code "183") (name "unconnected-(U5C-PE9{slash}FSMC_D6{slash}TIM1_CH1{slash}EVENTOUT-Pad40)") (class "Default")
      (node (ref "U5") (pin "40") (pinfunction "PE9/FSMC_D6/TIM1_CH1/EVENTOUT_40") (pintype "bidirectional"))
    )
    (net (code "184") (name "unconnected-(U5C-PE10{slash}FSMC_D7{slash}TIM1_CH2N{slash}EVENTOUT-Pad41)") (class "Default")
      (node (ref "U5") (pin "41") (pinfunction "PE10/FSMC_D7/TIM1_CH2N/EVENTOUT_41") (pintype "bidirectional"))
    )
    (net (code "185") (name "unconnected-(U5C-PE11{slash}FSMC_D8{slash}TIM1_CH2{slash}EVENTOUT-Pad42)") (class "Default")
      (node (ref "U5") (pin "42") (pinfunction "PE11/FSMC_D8/TIM1_CH2/EVENTOUT_42") (pintype "bidirectional"))
    )
    (net (code "186") (name "unconnected-(U5C-PE12{slash}FSMC_D9{slash}TIM1_CH3N{slash}EVENTOUT-Pad43)") (class "Default")
      (node (ref "U5") (pin "43") (pinfunction "PE12/FSMC_D9/TIM1_CH3N/EVENTOUT_43") (pintype "bidirectional"))
    )
    (net (code "187") (name "unconnected-(U5C-PE13{slash}FSMC_D10{slash}TIM1_CH3{slash}EVENTOUT-Pad44)") (class "Default")
      (node (ref "U5") (pin "44") (pinfunction "PE13/FSMC_D10/TIM1_CH3/EVENTOUT_44") (pintype "bidirectional"))
    )
    (net (code "188") (name "unconnected-(U5C-PE14{slash}FSMC_D11{slash}TIM1_CH4{slash}EVENTOUT-Pad45)") (class "Default")
      (node (ref "U5") (pin "45") (pinfunction "PE14/FSMC_D11/TIM1_CH4/EVENTOUT_45") (pintype "bidirectional"))
    )
    (net (code "189") (name "unconnected-(U5C-PE15{slash}FSMC_D12{slash}TIM1_BKIN{slash}EVENTOUT-Pad46)") (class "Default")
      (node (ref "U5") (pin "46") (pinfunction "PE15/FSMC_D12/TIM1_BKIN/EVENTOUT_46") (pintype "bidirectional"))
    )
    (net (code "190") (name "unconnected-(U5E-VBAT-Pad6)") (class "Default")
      (node (ref "U5") (pin "6") (pinfunction "VBAT_6") (pintype "power_in+no_connect"))
    )
    (net (code "191") (name "unconnected-(USB1-CC1-PadA5)") (class "Default")
      (node (ref "USB1") (pin "A5") (pinfunction "CC1_A5") (pintype "passive"))
    )
    (net (code "192") (name "unconnected-(USB1-CC2-PadB5)") (class "Default")
      (node (ref "USB1") (pin "B5") (pinfunction "CC2_B5") (pintype "passive"))
    )
    (net (code "193") (name "unconnected-(USB1-GND-PadA1)") (class "Default")
      (node (ref "USB1") (pin "A1") (pinfunction "GND_A1") (pintype "passive"))
    )
    (net (code "194") (name "unconnected-(USB1-GND-PadA12)") (class "Default")
      (node (ref "USB1") (pin "A12") (pinfunction "GND_A12") (pintype "passive"))
    )
    (net (code "195") (name "unconnected-(USB1-GND-PadB1)") (class "Default")
      (node (ref "USB1") (pin "B1") (pinfunction "GND_B1") (pintype "passive"))
    )
    (net (code "196") (name "unconnected-(USB1-GND-PadB12)") (class "Default")
      (node (ref "USB1") (pin "B12") (pinfunction "GND_B12") (pintype "passive"))
    )
    (net (code "197") (name "unconnected-(USB1-RX1+-PadB11)") (class "Default")
      (node (ref "USB1") (pin "B11") (pinfunction "RX1+_B11") (pintype "passive"))
    )
    (net (code "198") (name "unconnected-(USB1-RX1--PadB10)") (class "Default")
      (node (ref "USB1") (pin "B10") (pinfunction "RX1-_B10") (pintype "passive"))
    )
    (net (code "199") (name "unconnected-(USB1-RX2+-PadA11)") (class "Default")
      (node (ref "USB1") (pin "A11") (pinfunction "RX2+_A11") (pintype "passive"))
    )
    (net (code "200") (name "unconnected-(USB1-RX2--PadA10)") (class "Default")
      (node (ref "USB1") (pin "A10") (pinfunction "RX2-_A10") (pintype "passive"))
    )
    (net (code "201") (name "unconnected-(USB1-SBU1-PadA8)") (class "Default")
      (node (ref "USB1") (pin "A8") (pinfunction "SBU1_A8") (pintype "passive"))
    )
    (net (code "202") (name "unconnected-(USB1-SBU2-PadB8)") (class "Default")
      (node (ref "USB1") (pin "B8") (pinfunction "SBU2_B8") (pintype "passive"))
    )
    (net (code "203") (name "unconnected-(USB1-TX1+-PadA2)") (class "Default")
      (node (ref "USB1") (pin "A2") (pinfunction "TX1+_A2") (pintype "passive"))
    )
    (net (code "204") (name "unconnected-(USB1-TX1--PadA3)") (class "Default")
      (node (ref "USB1") (pin "A3") (pinfunction "TX1-_A3") (pintype "passive"))
    )
    (net (code "205") (name "unconnected-(USB1-TX2+-PadB2)") (class "Default")
      (node (ref "USB1") (pin "B2") (pinfunction "TX2+_B2") (pintype "passive"))
    )
    (net (code "206") (name "unconnected-(USB1-TX2--PadB3)") (class "Default")
      (node (ref "USB1") (pin "B3") (pinfunction "TX2-_B3") (pintype "passive"))
    )
    (net (code "207") (name "unconnected-(USB2-RX1+-PadB11)") (class "Default")
      (node (ref "USB2") (pin "B11") (pinfunction "RX1+_B11") (pintype "passive"))
    )
    (net (code "208") (name "unconnected-(USB2-RX1--PadB10)") (class "Default")
      (node (ref "USB2") (pin "B10") (pinfunction "RX1-_B10") (pintype "passive"))
    )
    (net (code "209") (name "unconnected-(USB2-RX2+-PadA11)") (class "Default")
      (node (ref "USB2") (pin "A11") (pinfunction "RX2+_A11") (pintype "passive"))
    )
    (net (code "210") (name "unconnected-(USB2-RX2--PadA10)") (class "Default")
      (node (ref "USB2") (pin "A10") (pinfunction "RX2-_A10") (pintype "passive"))
    )
    (net (code "211") (name "unconnected-(USB2-SBU1-PadA8)") (class "Default")
      (node (ref "USB2") (pin "A8") (pinfunction "SBU1_A8") (pintype "passive"))
    )
    (net (code "212") (name "unconnected-(USB2-SBU2-PadB8)") (class "Default")
      (node (ref "USB2") (pin "B8") (pinfunction "SBU2_B8") (pintype "passive"))
    )
    (net (code "213") (name "unconnected-(USB2-TX1+-PadA2)") (class "Default")
      (node (ref "USB2") (pin "A2") (pinfunction "TX1+_A2") (pintype "passive"))
    )
    (net (code "214") (name "unconnected-(USB2-TX1--PadA3)") (class "Default")
      (node (ref "USB2") (pin "A3") (pinfunction "TX1-_A3") (pintype "passive"))
    )
    (net (code "215") (name "unconnected-(USB2-TX2+-PadB2)") (class "Default")
      (node (ref "USB2") (pin "B2") (pinfunction "TX2+_B2") (pintype "passive"))
    )
    (net (code "216") (name "unconnected-(USB2-TX2--PadB3)") (class "Default")
      (node (ref "USB2") (pin "B3") (pinfunction "TX2-_B3") (pintype "passive"))
    )
  )
)
